# Dx32_V1_0.net
KiCad netlist of a schematic drawn in EAGLE
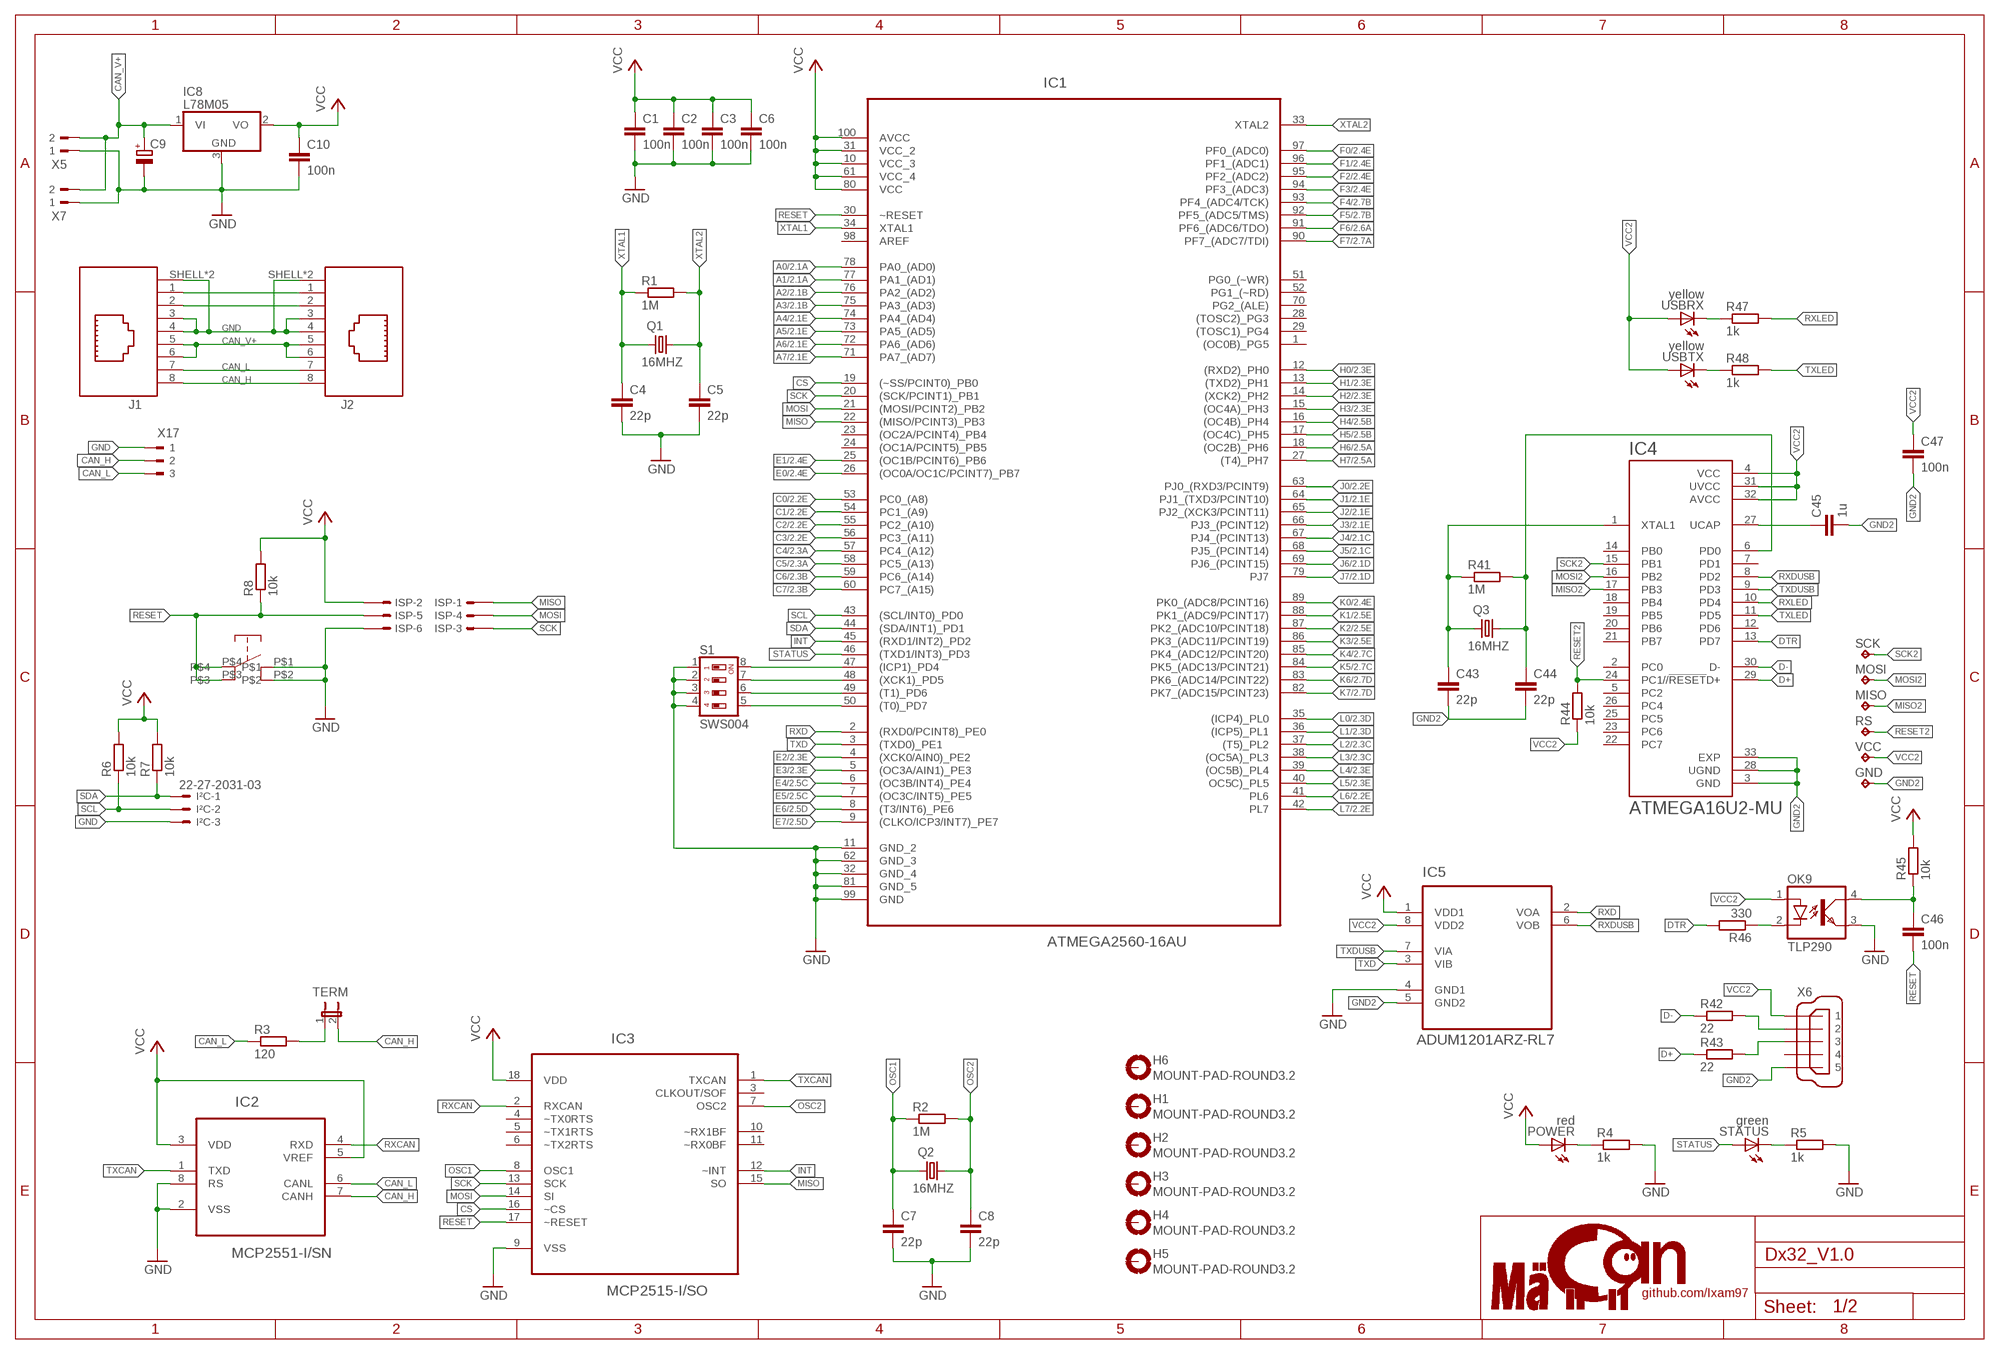
[diagram p0: schematic, sheet 1]
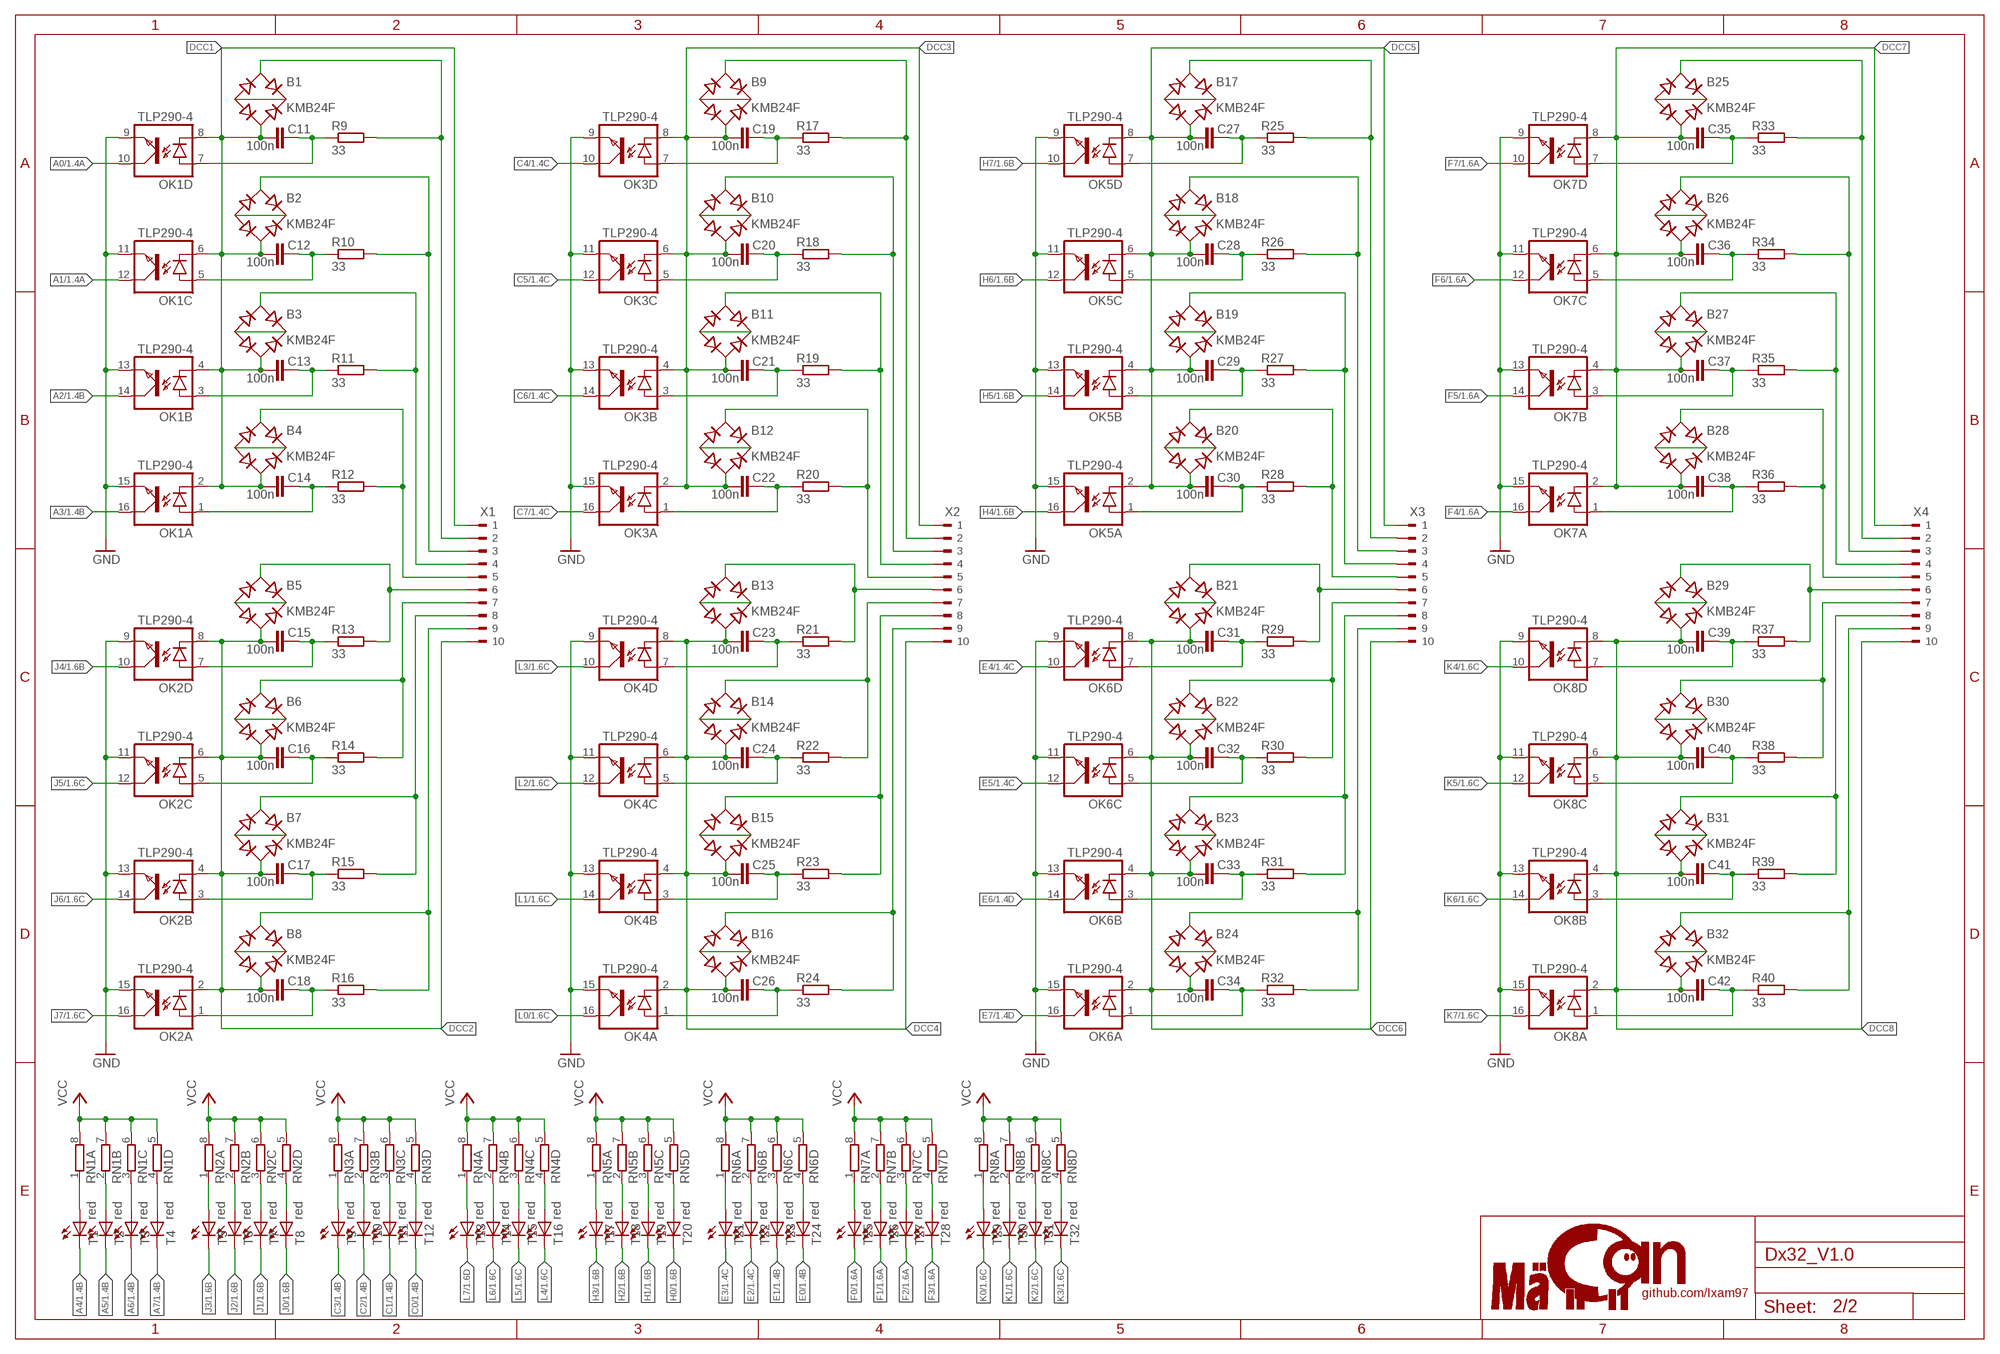
[diagram p1: schematic, sheet 2]

(export (version "E")
  (design (tool "Eeschema 10.0.6"))
  (components
    (comp (ref "C1")
      (value "100n")
      (footprint "eagle-import:C0402")
      (libsource (lib "eagle-import") (part "C-EUC0402"))
    )
    (comp (ref "C2")
      (value "100n")
      (footprint "eagle-import:C0402")
      (libsource (lib "eagle-import") (part "C-EUC0402"))
    )
    (comp (ref "C3")
      (value "100n")
      (footprint "eagle-import:C0402")
      (libsource (lib "eagle-import") (part "C-EUC0402"))
    )
    (comp (ref "C4")
      (value "22p")
      (footprint "eagle-import:C0402")
      (libsource (lib "eagle-import") (part "C-EUC0402"))
    )
    (comp (ref "C5")
      (value "22p")
      (footprint "eagle-import:C0402")
      (libsource (lib "eagle-import") (part "C-EUC0402"))
    )
    (comp (ref "C6")
      (value "100n")
      (footprint "eagle-import:C0402")
      (libsource (lib "eagle-import") (part "C-EUC0402"))
    )
    (comp (ref "C7")
      (value "22p")
      (footprint "eagle-import:C0402")
      (libsource (lib "eagle-import") (part "C-EUC0402"))
    )
    (comp (ref "C8")
      (value "22p")
      (footprint "eagle-import:C0402")
      (libsource (lib "eagle-import") (part "C-EUC0402"))
    )
    (comp (ref "C9")
      (value "CPOL-EUCT3216")
      (footprint "eagle-import:CT3216")
      (libsource (lib "eagle-import") (part "CPOL-EUCT3216"))
    )
    (comp (ref "C10")
      (value "100n")
      (footprint "eagle-import:C0402")
      (libsource (lib "eagle-import") (part "C-EUC0402"))
    )
    (comp (ref "C43")
      (value "22p")
      (footprint "eagle-import:C0402")
      (libsource (lib "eagle-import") (part "C-EUC0402"))
    )
    (comp (ref "C44")
      (value "22p")
      (footprint "eagle-import:C0402")
      (libsource (lib "eagle-import") (part "C-EUC0402"))
    )
    (comp (ref "C45")
      (value "1u")
      (footprint "eagle-import:C0402")
      (libsource (lib "eagle-import") (part "C-EUC0402"))
    )
    (comp (ref "C46")
      (value "100n")
      (footprint "eagle-import:C0402")
      (libsource (lib "eagle-import") (part "C-EUC0402"))
    )
    (comp (ref "C47")
      (value "100n")
      (footprint "eagle-import:C0402")
      (libsource (lib "eagle-import") (part "C-EUC0402"))
    )
    (comp (ref "GND")
      (value "TPB1,27")
      (footprint "eagle-import:B1,27")
      (libsource (lib "eagle-import") (part "TPB1,27"))
    )
    (comp (ref "H1")
      (value "MOUNT-PAD-ROUND3.2")
      (footprint "eagle-import:3,2-PAD")
      (libsource (lib "eagle-import") (part "MOUNT-PAD-ROUND3.2"))
    )
    (comp (ref "H2")
      (value "MOUNT-PAD-ROUND3.2")
      (footprint "eagle-import:3,2-PAD")
      (libsource (lib "eagle-import") (part "MOUNT-PAD-ROUND3.2"))
    )
    (comp (ref "H3")
      (value "MOUNT-PAD-ROUND3.2")
      (footprint "eagle-import:3,2-PAD")
      (libsource (lib "eagle-import") (part "MOUNT-PAD-ROUND3.2"))
    )
    (comp (ref "H4")
      (value "MOUNT-PAD-ROUND3.2")
      (footprint "eagle-import:3,2-PAD")
      (libsource (lib "eagle-import") (part "MOUNT-PAD-ROUND3.2"))
    )
    (comp (ref "H5")
      (value "MOUNT-PAD-ROUND3.2")
      (footprint "eagle-import:3,2-PAD")
      (libsource (lib "eagle-import") (part "MOUNT-PAD-ROUND3.2"))
    )
    (comp (ref "H6")
      (value "MOUNT-PAD-ROUND3.2")
      (footprint "eagle-import:3,2-PAD")
      (libsource (lib "eagle-import") (part "MOUNT-PAD-ROUND3.2"))
    )
    (comp (ref "IC1")
      (value "ATMEGA2560-16AU")
      (footprint "eagle-import:QFP50P1600X1600X120-100N")
      (fields (field (name "MF") "Microchip"))
      (libsource (lib "eagle-import") (part "ATMEGA2560-16AU"))
    )
    (comp (ref "IC2")
      (value "MCP2551-I/SN")
      (footprint "eagle-import:SOIC127P600X175-8N")
      (libsource (lib "eagle-import") (part "MCP2551-I/SN"))
    )
    (comp (ref "IC3")
      (value "MCP2515-I/SO")
      (footprint "eagle-import:SOIC127P1034X264-18N")
      (libsource (lib "eagle-import") (part "MCP2515-I/SO"))
    )
    (comp (ref "IC4")
      (value "ATMEGA16U2-MU")
      (footprint "eagle-import:QFN50P500X500X100-33N")
      (fields (field (name "MF") "Microchip"))
      (libsource (lib "eagle-import") (part "ATMEGA16U2-MU"))
    )
    (comp (ref "IC5")
      (value "ADUM1201ARZ-RL7")
      (footprint "eagle-import:SOIC127P600X175-8N")
      (fields (field (name "MF") "Analog Devices"))
      (libsource (lib "eagle-import") (part "ADUM1201ARZ-RL7"))
    )
    (comp (ref "IC8")
      (value "L78M05")
      (footprint "eagle-import:TO252")
      (fields (field (name "JLCPCB-PART") "C58069"))
      (libsource (lib "eagle-import") (part "78DT05"))
    )
    (comp (ref "ISP")
      (value "057-006-1")
      (footprint "eagle-import:057-006-1")
      (libsource (lib "eagle-import") (part "057-006-1"))
    )
    (comp (ref "I²C")
      (value "22-27-2031-03")
      (footprint "eagle-import:6410-03")
      (fields (field (name "MF") "MOLEX"))
      (libsource (lib "eagle-import") (part "22-?-0327-2031"))
    )
    (comp (ref "J1")
      (value "615008140421")
      (footprint "eagle-import:615008140421")
      (libsource (lib "eagle-import") (part "615008140421"))
    )
    (comp (ref "J2")
      (value "615008140421")
      (footprint "eagle-import:615008140421")
      (libsource (lib "eagle-import") (part "615008140421"))
    )
    (comp (ref "MISO")
      (value "TPB1,27")
      (footprint "eagle-import:B1,27")
      (libsource (lib "eagle-import") (part "TPB1,27"))
    )
    (comp (ref "MOSI")
      (value "TPB1,27")
      (footprint "eagle-import:B1,27")
      (libsource (lib "eagle-import") (part "TPB1,27"))
    )
    (comp (ref "OK9")
      (value "TLP290")
      (footprint "eagle-import:MINI-FLAT-4")
      (libsource (lib "eagle-import") (part "TLP283"))
    )
    (comp (ref "POWER")
      (value "red")
      (footprint "eagle-import:CHIP-LED0805")
      (libsource (lib "eagle-import") (part "LEDCHIP-LED0805"))
    )
    (comp (ref "Q1")
      (value "16MHZ")
      (footprint "eagle-import:3.2X2.5_KX-7")
      (libsource (lib "eagle-import") (part "KX-7"))
    )
    (comp (ref "Q2")
      (value "16MHZ")
      (footprint "eagle-import:3.2X2.5_KX-7")
      (libsource (lib "eagle-import") (part "KX-7"))
    )
    (comp (ref "Q3")
      (value "16MHZ")
      (footprint "eagle-import:3.2X2.5_KX-7")
      (libsource (lib "eagle-import") (part "KX-7"))
    )
    (comp (ref "R1")
      (value "1M")
      (footprint "eagle-import:R0402")
      (libsource (lib "eagle-import") (part "R-EU_R0402"))
    )
    (comp (ref "R2")
      (value "1M")
      (footprint "eagle-import:R0402")
      (libsource (lib "eagle-import") (part "R-EU_R0402"))
    )
    (comp (ref "R3")
      (value "120")
      (footprint "eagle-import:R0402")
      (libsource (lib "eagle-import") (part "R-EU_R0402"))
    )
    (comp (ref "R4")
      (value "1k")
      (footprint "eagle-import:R0402")
      (libsource (lib "eagle-import") (part "R-EU_R0402"))
    )
    (comp (ref "R5")
      (value "1k")
      (footprint "eagle-import:R0402")
      (libsource (lib "eagle-import") (part "R-EU_R0402"))
    )
    (comp (ref "R6")
      (value "10k")
      (footprint "eagle-import:R0402")
      (libsource (lib "eagle-import") (part "R-EU_R0402"))
    )
    (comp (ref "R7")
      (value "10k")
      (footprint "eagle-import:R0402")
      (libsource (lib "eagle-import") (part "R-EU_R0402"))
    )
    (comp (ref "R8")
      (value "10k")
      (footprint "eagle-import:R0402")
      (libsource (lib "eagle-import") (part "R-EU_R0402"))
    )
    (comp (ref "R41")
      (value "1M")
      (footprint "eagle-import:R0402")
      (libsource (lib "eagle-import") (part "R-EU_R0402"))
    )
    (comp (ref "R42")
      (value "22")
      (footprint "eagle-import:R0402")
      (libsource (lib "eagle-import") (part "R-EU_R0402"))
    )
    (comp (ref "R43")
      (value "22")
      (footprint "eagle-import:R0402")
      (libsource (lib "eagle-import") (part "R-EU_R0402"))
    )
    (comp (ref "R44")
      (value "10k")
      (footprint "eagle-import:R0402")
      (libsource (lib "eagle-import") (part "R-EU_R0402"))
    )
    (comp (ref "R45")
      (value "10k")
      (footprint "eagle-import:R0402")
      (libsource (lib "eagle-import") (part "R-EU_R0402"))
    )
    (comp (ref "R46")
      (value "330")
      (footprint "eagle-import:R0402")
      (libsource (lib "eagle-import") (part "R-EU_R0402"))
    )
    (comp (ref "R47")
      (value "1k")
      (footprint "eagle-import:R0402")
      (libsource (lib "eagle-import") (part "R-EU_R0402"))
    )
    (comp (ref "R48")
      (value "1k")
      (footprint "eagle-import:R0402")
      (libsource (lib "eagle-import") (part "R-EU_R0402"))
    )
    (comp (ref "RS")
      (value "TPB1,27")
      (footprint "eagle-import:B1,27")
      (libsource (lib "eagle-import") (part "TPB1,27"))
    )
    (comp (ref "S1")
      (value "SWS004")
      (footprint "eagle-import:SMS-004")
      (libsource (lib "eagle-import") (part "SWS004"))
    )
    (comp (ref "SCK")
      (value "TPB1,27")
      (footprint "eagle-import:B1,27")
      (libsource (lib "eagle-import") (part "TPB1,27"))
    )
    (comp (ref "STATUS")
      (value "green")
      (footprint "eagle-import:CHIP-LED0805")
      (libsource (lib "eagle-import") (part "LEDCHIP-LED0805"))
    )
    (comp (ref "TERM")
      (value "JP1E")
      (footprint "eagle-import:JP1")
      (libsource (lib "eagle-import") (part "JP1E"))
    )
    (comp (ref "U$15")
      (value "BUTTON_JLC")
      (footprint "eagle-import:BUTTON")
      (libsource (lib "eagle-import") (part "BUTTON_JLC"))
    )
    (comp (ref "USBRX")
      (value "yellow")
      (footprint "eagle-import:CHIP-LED0805")
      (libsource (lib "eagle-import") (part "LEDCHIP-LED0805"))
    )
    (comp (ref "USBTX")
      (value "yellow")
      (footprint "eagle-import:CHIP-LED0805")
      (libsource (lib "eagle-import") (part "LEDCHIP-LED0805"))
    )
    (comp (ref "VCC")
      (value "TPB1,27")
      (footprint "eagle-import:B1,27")
      (libsource (lib "eagle-import") (part "TPB1,27"))
    )
    (comp (ref "X5")
      (value "180-2")
      (footprint "eagle-import:180-2")
      (libsource (lib "eagle-import") (part "180-2"))
    )
    (comp (ref "X6")
      (value "MINI-USB_SHIELD5P2-32005-601")
      (footprint "eagle-import:32005-601")
      (libsource (lib "eagle-import") (part "MINI-USB_SHIELD5P2-32005-601"))
    )
    (comp (ref "X7")
      (value "180-2")
      (footprint "eagle-import:180-2")
      (libsource (lib "eagle-import") (part "180-2"))
    )
    (comp (ref "X17")
      (value "180-3")
      (footprint "eagle-import:180-3")
      (libsource (lib "eagle-import") (part "180-3"))
    )
    (comp (ref "B1")
      (value "KMB24F")
      (footprint "eagle-import:MBS")
      (fields (field (name "JLCPCB-PART") "C113927"))
      (libsource (lib "eagle-import") (part "BS2"))
    )
    (comp (ref "B2")
      (value "KMB24F")
      (footprint "eagle-import:MBS")
      (libsource (lib "eagle-import") (part "BS2"))
    )
    (comp (ref "B3")
      (value "KMB24F")
      (footprint "eagle-import:MBS")
      (libsource (lib "eagle-import") (part "BS2"))
    )
    (comp (ref "B4")
      (value "KMB24F")
      (footprint "eagle-import:MBS")
      (libsource (lib "eagle-import") (part "BS2"))
    )
    (comp (ref "B5")
      (value "KMB24F")
      (footprint "eagle-import:MBS")
      (libsource (lib "eagle-import") (part "BS2"))
    )
    (comp (ref "B6")
      (value "KMB24F")
      (footprint "eagle-import:MBS")
      (libsource (lib "eagle-import") (part "BS2"))
    )
    (comp (ref "B7")
      (value "KMB24F")
      (footprint "eagle-import:MBS")
      (libsource (lib "eagle-import") (part "BS2"))
    )
    (comp (ref "B8")
      (value "KMB24F")
      (footprint "eagle-import:MBS")
      (libsource (lib "eagle-import") (part "BS2"))
    )
    (comp (ref "B9")
      (value "KMB24F")
      (footprint "eagle-import:MBS")
      (libsource (lib "eagle-import") (part "BS2"))
    )
    (comp (ref "B10")
      (value "KMB24F")
      (footprint "eagle-import:MBS")
      (libsource (lib "eagle-import") (part "BS2"))
    )
    (comp (ref "B11")
      (value "KMB24F")
      (footprint "eagle-import:MBS")
      (libsource (lib "eagle-import") (part "BS2"))
    )
    (comp (ref "B12")
      (value "KMB24F")
      (footprint "eagle-import:MBS")
      (libsource (lib "eagle-import") (part "BS2"))
    )
    (comp (ref "B13")
      (value "KMB24F")
      (footprint "eagle-import:MBS")
      (libsource (lib "eagle-import") (part "BS2"))
    )
    (comp (ref "B14")
      (value "KMB24F")
      (footprint "eagle-import:MBS")
      (libsource (lib "eagle-import") (part "BS2"))
    )
    (comp (ref "B15")
      (value "KMB24F")
      (footprint "eagle-import:MBS")
      (libsource (lib "eagle-import") (part "BS2"))
    )
    (comp (ref "B16")
      (value "KMB24F")
      (footprint "eagle-import:MBS")
      (libsource (lib "eagle-import") (part "BS2"))
    )
    (comp (ref "B17")
      (value "KMB24F")
      (footprint "eagle-import:MBS")
      (libsource (lib "eagle-import") (part "BS2"))
    )
    (comp (ref "B18")
      (value "KMB24F")
      (footprint "eagle-import:MBS")
      (libsource (lib "eagle-import") (part "BS2"))
    )
    (comp (ref "B19")
      (value "KMB24F")
      (footprint "eagle-import:MBS")
      (libsource (lib "eagle-import") (part "BS2"))
    )
    (comp (ref "B20")
      (value "KMB24F")
      (footprint "eagle-import:MBS")
      (libsource (lib "eagle-import") (part "BS2"))
    )
    (comp (ref "B21")
      (value "KMB24F")
      (footprint "eagle-import:MBS")
      (libsource (lib "eagle-import") (part "BS2"))
    )
    (comp (ref "B22")
      (value "KMB24F")
      (footprint "eagle-import:MBS")
      (libsource (lib "eagle-import") (part "BS2"))
    )
    (comp (ref "B23")
      (value "KMB24F")
      (footprint "eagle-import:MBS")
      (libsource (lib "eagle-import") (part "BS2"))
    )
    (comp (ref "B24")
      (value "KMB24F")
      (footprint "eagle-import:MBS")
      (libsource (lib "eagle-import") (part "BS2"))
    )
    (comp (ref "B25")
      (value "KMB24F")
      (footprint "eagle-import:MBS")
      (libsource (lib "eagle-import") (part "BS2"))
    )
    (comp (ref "B26")
      (value "KMB24F")
      (footprint "eagle-import:MBS")
      (libsource (lib "eagle-import") (part "BS2"))
    )
    (comp (ref "B27")
      (value "KMB24F")
      (footprint "eagle-import:MBS")
      (libsource (lib "eagle-import") (part "BS2"))
    )
    (comp (ref "B28")
      (value "KMB24F")
      (footprint "eagle-import:MBS")
      (libsource (lib "eagle-import") (part "BS2"))
    )
    (comp (ref "B29")
      (value "KMB24F")
      (footprint "eagle-import:MBS")
      (libsource (lib "eagle-import") (part "BS2"))
    )
    (comp (ref "B30")
      (value "KMB24F")
      (footprint "eagle-import:MBS")
      (libsource (lib "eagle-import") (part "BS2"))
    )
    (comp (ref "B31")
      (value "KMB24F")
      (footprint "eagle-import:MBS")
      (libsource (lib "eagle-import") (part "BS2"))
    )
    (comp (ref "B32")
      (value "KMB24F")
      (footprint "eagle-import:MBS")
      (libsource (lib "eagle-import") (part "BS2"))
    )
    (comp (ref "C11")
      (value "100n")
      (footprint "eagle-import:C0402")
      (libsource (lib "eagle-import") (part "C-EUC0402"))
    )
    (comp (ref "C12")
      (value "100n")
      (footprint "eagle-import:C0402")
      (libsource (lib "eagle-import") (part "C-EUC0402"))
    )
    (comp (ref "C13")
      (value "100n")
      (footprint "eagle-import:C0402")
      (libsource (lib "eagle-import") (part "C-EUC0402"))
    )
    (comp (ref "C14")
      (value "100n")
      (footprint "eagle-import:C0402")
      (libsource (lib "eagle-import") (part "C-EUC0402"))
    )
    (comp (ref "C15")
      (value "100n")
      (footprint "eagle-import:C0402")
      (libsource (lib "eagle-import") (part "C-EUC0402"))
    )
    (comp (ref "C16")
      (value "100n")
      (footprint "eagle-import:C0402")
      (libsource (lib "eagle-import") (part "C-EUC0402"))
    )
    (comp (ref "C17")
      (value "100n")
      (footprint "eagle-import:C0402")
      (libsource (lib "eagle-import") (part "C-EUC0402"))
    )
    (comp (ref "C18")
      (value "100n")
      (footprint "eagle-import:C0402")
      (libsource (lib "eagle-import") (part "C-EUC0402"))
    )
    (comp (ref "C19")
      (value "100n")
      (footprint "eagle-import:C0402")
      (libsource (lib "eagle-import") (part "C-EUC0402"))
    )
    (comp (ref "C20")
      (value "100n")
      (footprint "eagle-import:C0402")
      (libsource (lib "eagle-import") (part "C-EUC0402"))
    )
    (comp (ref "C21")
      (value "100n")
      (footprint "eagle-import:C0402")
      (libsource (lib "eagle-import") (part "C-EUC0402"))
    )
    (comp (ref "C22")
      (value "100n")
      (footprint "eagle-import:C0402")
      (libsource (lib "eagle-import") (part "C-EUC0402"))
    )
    (comp (ref "C23")
      (value "100n")
      (footprint "eagle-import:C0402")
      (libsource (lib "eagle-import") (part "C-EUC0402"))
    )
    (comp (ref "C24")
      (value "100n")
      (footprint "eagle-import:C0402")
      (libsource (lib "eagle-import") (part "C-EUC0402"))
    )
    (comp (ref "C25")
      (value "100n")
      (footprint "eagle-import:C0402")
      (libsource (lib "eagle-import") (part "C-EUC0402"))
    )
    (comp (ref "C26")
      (value "100n")
      (footprint "eagle-import:C0402")
      (libsource (lib "eagle-import") (part "C-EUC0402"))
    )
    (comp (ref "C27")
      (value "100n")
      (footprint "eagle-import:C0402")
      (libsource (lib "eagle-import") (part "C-EUC0402"))
    )
    (comp (ref "C28")
      (value "100n")
      (footprint "eagle-import:C0402")
      (libsource (lib "eagle-import") (part "C-EUC0402"))
    )
    (comp (ref "C29")
      (value "100n")
      (footprint "eagle-import:C0402")
      (libsource (lib "eagle-import") (part "C-EUC0402"))
    )
    (comp (ref "C30")
      (value "100n")
      (footprint "eagle-import:C0402")
      (libsource (lib "eagle-import") (part "C-EUC0402"))
    )
    (comp (ref "C31")
      (value "100n")
      (footprint "eagle-import:C0402")
      (libsource (lib "eagle-import") (part "C-EUC0402"))
    )
    (comp (ref "C32")
      (value "100n")
      (footprint "eagle-import:C0402")
      (libsource (lib "eagle-import") (part "C-EUC0402"))
    )
    (comp (ref "C33")
      (value "100n")
      (footprint "eagle-import:C0402")
      (libsource (lib "eagle-import") (part "C-EUC0402"))
    )
    (comp (ref "C34")
      (value "100n")
      (footprint "eagle-import:C0402")
      (libsource (lib "eagle-import") (part "C-EUC0402"))
    )
    (comp (ref "C35")
      (value "100n")
      (footprint "eagle-import:C0402")
      (libsource (lib "eagle-import") (part "C-EUC0402"))
    )
    (comp (ref "C36")
      (value "100n")
      (footprint "eagle-import:C0402")
      (libsource (lib "eagle-import") (part "C-EUC0402"))
    )
    (comp (ref "C37")
      (value "100n")
      (footprint "eagle-import:C0402")
      (libsource (lib "eagle-import") (part "C-EUC0402"))
    )
    (comp (ref "C38")
      (value "100n")
      (footprint "eagle-import:C0402")
      (libsource (lib "eagle-import") (part "C-EUC0402"))
    )
    (comp (ref "C39")
      (value "100n")
      (footprint "eagle-import:C0402")
      (libsource (lib "eagle-import") (part "C-EUC0402"))
    )
    (comp (ref "C40")
      (value "100n")
      (footprint "eagle-import:C0402")
      (libsource (lib "eagle-import") (part "C-EUC0402"))
    )
    (comp (ref "C41")
      (value "100n")
      (footprint "eagle-import:C0402")
      (libsource (lib "eagle-import") (part "C-EUC0402"))
    )
    (comp (ref "C42")
      (value "100n")
      (footprint "eagle-import:C0402")
      (libsource (lib "eagle-import") (part "C-EUC0402"))
    )
    (comp (ref "OK1")
      (value "TLP290-4")
      (footprint "eagle-import:MINI-FLAT-16")
      (fields (field (name "JLCPC-PART") "C39031"))
      (libsource (lib "eagle-import") (part "TLP283-4"))
    )
    (comp (ref "OK2")
      (value "TLP290-4")
      (footprint "eagle-import:MINI-FLAT-16")
      (libsource (lib "eagle-import") (part "TLP283-4"))
    )
    (comp (ref "OK3")
      (value "TLP290-4")
      (footprint "eagle-import:MINI-FLAT-16")
      (libsource (lib "eagle-import") (part "TLP283-4"))
    )
    (comp (ref "OK4")
      (value "TLP290-4")
      (footprint "eagle-import:MINI-FLAT-16")
      (libsource (lib "eagle-import") (part "TLP283-4"))
    )
    (comp (ref "OK5")
      (value "TLP290-4")
      (footprint "eagle-import:MINI-FLAT-16")
      (libsource (lib "eagle-import") (part "TLP283-4"))
    )
    (comp (ref "OK6")
      (value "TLP290-4")
      (footprint "eagle-import:MINI-FLAT-16")
      (libsource (lib "eagle-import") (part "TLP283-4"))
    )
    (comp (ref "OK7")
      (value "TLP290-4")
      (footprint "eagle-import:MINI-FLAT-16")
      (libsource (lib "eagle-import") (part "TLP283-4"))
    )
    (comp (ref "OK8")
      (value "TLP290-4")
      (footprint "eagle-import:MINI-FLAT-16")
      (libsource (lib "eagle-import") (part "TLP283-4"))
    )
    (comp (ref "R9")
      (value "33")
      (footprint "eagle-import:R0402")
      (libsource (lib "eagle-import") (part "R-EU_R0402"))
    )
    (comp (ref "R10")
      (value "33")
      (footprint "eagle-import:R0402")
      (libsource (lib "eagle-import") (part "R-EU_R0402"))
    )
    (comp (ref "R11")
      (value "33")
      (footprint "eagle-import:R0402")
      (libsource (lib "eagle-import") (part "R-EU_R0402"))
    )
    (comp (ref "R12")
      (value "33")
      (footprint "eagle-import:R0402")
      (libsource (lib "eagle-import") (part "R-EU_R0402"))
    )
    (comp (ref "R13")
      (value "33")
      (footprint "eagle-import:R0402")
      (libsource (lib "eagle-import") (part "R-EU_R0402"))
    )
    (comp (ref "R14")
      (value "33")
      (footprint "eagle-import:R0402")
      (libsource (lib "eagle-import") (part "R-EU_R0402"))
    )
    (comp (ref "R15")
      (value "33")
      (footprint "eagle-import:R0402")
      (libsource (lib "eagle-import") (part "R-EU_R0402"))
    )
    (comp (ref "R16")
      (value "33")
      (footprint "eagle-import:R0402")
      (libsource (lib "eagle-import") (part "R-EU_R0402"))
    )
    (comp (ref "R17")
      (value "33")
      (footprint "eagle-import:R0402")
      (libsource (lib "eagle-import") (part "R-EU_R0402"))
    )
    (comp (ref "R18")
      (value "33")
      (footprint "eagle-import:R0402")
      (libsource (lib "eagle-import") (part "R-EU_R0402"))
    )
    (comp (ref "R19")
      (value "33")
      (footprint "eagle-import:R0402")
      (libsource (lib "eagle-import") (part "R-EU_R0402"))
    )
    (comp (ref "R20")
      (value "33")
      (footprint "eagle-import:R0402")
      (libsource (lib "eagle-import") (part "R-EU_R0402"))
    )
    (comp (ref "R21")
      (value "33")
      (footprint "eagle-import:R0402")
      (libsource (lib "eagle-import") (part "R-EU_R0402"))
    )
    (comp (ref "R22")
      (value "33")
      (footprint "eagle-import:R0402")
      (libsource (lib "eagle-import") (part "R-EU_R0402"))
    )
    (comp (ref "R23")
      (value "33")
      (footprint "eagle-import:R0402")
      (libsource (lib "eagle-import") (part "R-EU_R0402"))
    )
    (comp (ref "R24")
      (value "33")
      (footprint "eagle-import:R0402")
      (libsource (lib "eagle-import") (part "R-EU_R0402"))
    )
    (comp (ref "R25")
      (value "33")
      (footprint "eagle-import:R0402")
      (libsource (lib "eagle-import") (part "R-EU_R0402"))
    )
    (comp (ref "R26")
      (value "33")
      (footprint "eagle-import:R0402")
      (libsource (lib "eagle-import") (part "R-EU_R0402"))
    )
    (comp (ref "R27")
      (value "33")
      (footprint "eagle-import:R0402")
      (libsource (lib "eagle-import") (part "R-EU_R0402"))
    )
    (comp (ref "R28")
      (value "33")
      (footprint "eagle-import:R0402")
      (libsource (lib "eagle-import") (part "R-EU_R0402"))
    )
    (comp (ref "R29")
      (value "33")
      (footprint "eagle-import:R0402")
      (libsource (lib "eagle-import") (part "R-EU_R0402"))
    )
    (comp (ref "R30")
      (value "33")
      (footprint "eagle-import:R0402")
      (libsource (lib "eagle-import") (part "R-EU_R0402"))
    )
    (comp (ref "R31")
      (value "33")
      (footprint "eagle-import:R0402")
      (libsource (lib "eagle-import") (part "R-EU_R0402"))
    )
    (comp (ref "R32")
      (value "33")
      (footprint "eagle-import:R0402")
      (libsource (lib "eagle-import") (part "R-EU_R0402"))
    )
    (comp (ref "R33")
      (value "33")
      (footprint "eagle-import:R0402")
      (libsource (lib "eagle-import") (part "R-EU_R0402"))
    )
    (comp (ref "R34")
      (value "33")
      (footprint "eagle-import:R0402")
      (libsource (lib "eagle-import") (part "R-EU_R0402"))
    )
    (comp (ref "R35")
      (value "33")
      (footprint "eagle-import:R0402")
      (libsource (lib "eagle-import") (part "R-EU_R0402"))
    )
    (comp (ref "R36")
      (value "33")
      (footprint "eagle-import:R0402")
      (libsource (lib "eagle-import") (part "R-EU_R0402"))
    )
    (comp (ref "R37")
      (value "33")
      (footprint "eagle-import:R0402")
      (libsource (lib "eagle-import") (part "R-EU_R0402"))
    )
    (comp (ref "R38")
      (value "33")
      (footprint "eagle-import:R0402")
      (libsource (lib "eagle-import") (part "R-EU_R0402"))
    )
    (comp (ref "R39")
      (value "33")
      (footprint "eagle-import:R0402")
      (libsource (lib "eagle-import") (part "R-EU_R0402"))
    )
    (comp (ref "R40")
      (value "33")
      (footprint "eagle-import:R0402")
      (libsource (lib "eagle-import") (part "R-EU_R0402"))
    )
    (comp (ref "RN1")
      (value "4R-N0603-ARV")
      (footprint "eagle-import:0603-ARV")
      (libsource (lib "eagle-import") (part "4R-N0603-ARV"))
    )
    (comp (ref "RN2")
      (value "4R-N0603-ARV")
      (footprint "eagle-import:0603-ARV")
      (libsource (lib "eagle-import") (part "4R-N0603-ARV"))
    )
    (comp (ref "RN3")
      (value "4R-N0603-ARV")
      (footprint "eagle-import:0603-ARV")
      (libsource (lib "eagle-import") (part "4R-N0603-ARV"))
    )
    (comp (ref "RN4")
      (value "4R-N0603-ARV")
      (footprint "eagle-import:0603-ARV")
      (libsource (lib "eagle-import") (part "4R-N0603-ARV"))
    )
    (comp (ref "RN5")
      (value "4R-N0603-ARV")
      (footprint "eagle-import:0603-ARV")
      (libsource (lib "eagle-import") (part "4R-N0603-ARV"))
    )
    (comp (ref "RN6")
      (value "4R-N0603-ARV")
      (footprint "eagle-import:0603-ARV")
      (libsource (lib "eagle-import") (part "4R-N0603-ARV"))
    )
    (comp (ref "RN7")
      (value "4R-N0603-ARV")
      (footprint "eagle-import:0603-ARV")
      (libsource (lib "eagle-import") (part "4R-N0603-ARV"))
    )
    (comp (ref "RN8")
      (value "4R-N0603-ARV")
      (footprint "eagle-import:0603-ARV")
      (libsource (lib "eagle-import") (part "4R-N0603-ARV"))
    )
    (comp (ref "T1")
      (value "red")
      (footprint "eagle-import:CHIP-LED0805")
      (fields (field (name "JLCPCB-PART") "C84256"))
      (libsource (lib "eagle-import") (part "LEDCHIP-LED0805"))
    )
    (comp (ref "T2")
      (value "red")
      (footprint "eagle-import:CHIP-LED0805")
      (libsource (lib "eagle-import") (part "LEDCHIP-LED0805"))
    )
    (comp (ref "T3")
      (value "red")
      (footprint "eagle-import:CHIP-LED0805")
      (libsource (lib "eagle-import") (part "LEDCHIP-LED0805"))
    )
    (comp (ref "T4")
      (value "red")
      (footprint "eagle-import:CHIP-LED0805")
      (libsource (lib "eagle-import") (part "LEDCHIP-LED0805"))
    )
    (comp (ref "T5")
      (value "red")
      (footprint "eagle-import:CHIP-LED0805")
      (libsource (lib "eagle-import") (part "LEDCHIP-LED0805"))
    )
    (comp (ref "T6")
      (value "red")
      (footprint "eagle-import:CHIP-LED0805")
      (libsource (lib "eagle-import") (part "LEDCHIP-LED0805"))
    )
    (comp (ref "T7")
      (value "red")
      (footprint "eagle-import:CHIP-LED0805")
      (libsource (lib "eagle-import") (part "LEDCHIP-LED0805"))
    )
    (comp (ref "T8")
      (value "red")
      (footprint "eagle-import:CHIP-LED0805")
      (libsource (lib "eagle-import") (part "LEDCHIP-LED0805"))
    )
    (comp (ref "T9")
      (value "red")
      (footprint "eagle-import:CHIP-LED0805")
      (libsource (lib "eagle-import") (part "LEDCHIP-LED0805"))
    )
    (comp (ref "T10")
      (value "red")
      (footprint "eagle-import:CHIP-LED0805")
      (libsource (lib "eagle-import") (part "LEDCHIP-LED0805"))
    )
    (comp (ref "T11")
      (value "red")
      (footprint "eagle-import:CHIP-LED0805")
      (libsource (lib "eagle-import") (part "LEDCHIP-LED0805"))
    )
    (comp (ref "T12")
      (value "red")
      (footprint "eagle-import:CHIP-LED0805")
      (libsource (lib "eagle-import") (part "LEDCHIP-LED0805"))
    )
    (comp (ref "T13")
      (value "red")
      (footprint "eagle-import:CHIP-LED0805")
      (libsource (lib "eagle-import") (part "LEDCHIP-LED0805"))
    )
    (comp (ref "T14")
      (value "red")
      (footprint "eagle-import:CHIP-LED0805")
      (libsource (lib "eagle-import") (part "LEDCHIP-LED0805"))
    )
    (comp (ref "T15")
      (value "red")
      (footprint "eagle-import:CHIP-LED0805")
      (libsource (lib "eagle-import") (part "LEDCHIP-LED0805"))
    )
    (comp (ref "T16")
      (value "red")
      (footprint "eagle-import:CHIP-LED0805")
      (libsource (lib "eagle-import") (part "LEDCHIP-LED0805"))
    )
    (comp (ref "T17")
      (value "red")
      (footprint "eagle-import:CHIP-LED0805")
      (libsource (lib "eagle-import") (part "LEDCHIP-LED0805"))
    )
    (comp (ref "T18")
      (value "red")
      (footprint "eagle-import:CHIP-LED0805")
      (libsource (lib "eagle-import") (part "LEDCHIP-LED0805"))
    )
    (comp (ref "T19")
      (value "red")
      (footprint "eagle-import:CHIP-LED0805")
      (libsource (lib "eagle-import") (part "LEDCHIP-LED0805"))
    )
    (comp (ref "T20")
      (value "red")
      (footprint "eagle-import:CHIP-LED0805")
      (libsource (lib "eagle-import") (part "LEDCHIP-LED0805"))
    )
    (comp (ref "T21")
      (value "red")
      (footprint "eagle-import:CHIP-LED0805")
      (libsource (lib "eagle-import") (part "LEDCHIP-LED0805"))
    )
    (comp (ref "T22")
      (value "red")
      (footprint "eagle-import:CHIP-LED0805")
      (libsource (lib "eagle-import") (part "LEDCHIP-LED0805"))
    )
    (comp (ref "T23")
      (value "red")
      (footprint "eagle-import:CHIP-LED0805")
      (libsource (lib "eagle-import") (part "LEDCHIP-LED0805"))
    )
    (comp (ref "T24")
      (value "red")
      (footprint "eagle-import:CHIP-LED0805")
      (libsource (lib "eagle-import") (part "LEDCHIP-LED0805"))
    )
    (comp (ref "T25")
      (value "red")
      (footprint "eagle-import:CHIP-LED0805")
      (libsource (lib "eagle-import") (part "LEDCHIP-LED0805"))
    )
    (comp (ref "T26")
      (value "red")
      (footprint "eagle-import:CHIP-LED0805")
      (libsource (lib "eagle-import") (part "LEDCHIP-LED0805"))
    )
    (comp (ref "T27")
      (value "red")
      (footprint "eagle-import:CHIP-LED0805")
      (libsource (lib "eagle-import") (part "LEDCHIP-LED0805"))
    )
    (comp (ref "T28")
      (value "red")
      (footprint "eagle-import:CHIP-LED0805")
      (libsource (lib "eagle-import") (part "LEDCHIP-LED0805"))
    )
    (comp (ref "T29")
      (value "red")
      (footprint "eagle-import:CHIP-LED0805")
      (libsource (lib "eagle-import") (part "LEDCHIP-LED0805"))
    )
    (comp (ref "T30")
      (value "red")
      (footprint "eagle-import:CHIP-LED0805")
      (libsource (lib "eagle-import") (part "LEDCHIP-LED0805"))
    )
    (comp (ref "T31")
      (value "red")
      (footprint "eagle-import:CHIP-LED0805")
      (libsource (lib "eagle-import") (part "LEDCHIP-LED0805"))
    )
    (comp (ref "T32")
      (value "red")
      (footprint "eagle-import:CHIP-LED0805")
      (libsource (lib "eagle-import") (part "LEDCHIP-LED0805"))
    )
    (comp (ref "X1")
      (value "180-10")
      (footprint "eagle-import:180-10")
      (libsource (lib "eagle-import") (part "180-10"))
    )
    (comp (ref "X2")
      (value "180-10")
      (footprint "eagle-import:180-10")
      (libsource (lib "eagle-import") (part "180-10"))
    )
    (comp (ref "X3")
      (value "180-10")
      (footprint "eagle-import:180-10")
      (libsource (lib "eagle-import") (part "180-10"))
    )
    (comp (ref "X4")
      (value "180-10")
      (footprint "eagle-import:180-10")
      (libsource (lib "eagle-import") (part "180-10"))
    )
  )
  (nets
    (net (code "1") (name "A0") (class "Default")
      (node (ref "IC1") (pin "78") (pinfunction "PA0_(AD0)_78") (pintype "bidirectional"))
      (node (ref "OK1") (pin "10") (pinfunction "COL_10") (pintype "passive"))
    )
    (net (code "2") (name "A1") (class "Default")
      (node (ref "IC1") (pin "77") (pinfunction "PA1_(AD1)_77") (pintype "bidirectional"))
      (node (ref "OK1") (pin "12") (pinfunction "COL_12") (pintype "passive"))
    )
    (net (code "3") (name "A2") (class "Default")
      (node (ref "IC1") (pin "76") (pinfunction "PA2_(AD2)_76") (pintype "bidirectional"))
      (node (ref "OK1") (pin "14") (pinfunction "COL_14") (pintype "passive"))
    )
    (net (code "4") (name "A3") (class "Default")
      (node (ref "IC1") (pin "75") (pinfunction "PA3_(AD3)_75") (pintype "bidirectional"))
      (node (ref "OK1") (pin "16") (pinfunction "COL_16") (pintype "passive"))
    )
    (net (code "5") (name "A4") (class "Default")
      (node (ref "IC1") (pin "74") (pinfunction "PA4_(AD4)_74") (pintype "bidirectional"))
      (node (ref "T1") (pin "C") (pinfunction "C_C") (pintype "passive"))
    )
    (net (code "6") (name "A5") (class "Default")
      (node (ref "IC1") (pin "73") (pinfunction "PA5_(AD5)_73") (pintype "bidirectional"))
      (node (ref "T2") (pin "C") (pinfunction "C_C") (pintype "passive"))
    )
    (net (code "7") (name "A6") (class "Default")
      (node (ref "IC1") (pin "72") (pinfunction "PA6_(AD6)_72") (pintype "bidirectional"))
      (node (ref "T3") (pin "C") (pinfunction "C_C") (pintype "passive"))
    )
    (net (code "8") (name "A7") (class "Default")
      (node (ref "IC1") (pin "71") (pinfunction "PA7_(AD7)_71") (pintype "bidirectional"))
      (node (ref "T4") (pin "C") (pinfunction "C_C") (pintype "passive"))
    )
    (net (code "9") (name "C0") (class "Default")
      (node (ref "IC1") (pin "53") (pinfunction "PC0_(A8)_53") (pintype "bidirectional"))
      (node (ref "T12") (pin "C") (pinfunction "C_C") (pintype "passive"))
    )
    (net (code "10") (name "C1") (class "Default")
      (node (ref "IC1") (pin "54") (pinfunction "PC1_(A9)_54") (pintype "bidirectional"))
      (node (ref "T11") (pin "C") (pinfunction "C_C") (pintype "passive"))
    )
    (net (code "11") (name "C2") (class "Default")
      (node (ref "IC1") (pin "55") (pinfunction "PC2_(A10)_55") (pintype "bidirectional"))
      (node (ref "T10") (pin "C") (pinfunction "C_C") (pintype "passive"))
    )
    (net (code "12") (name "C3") (class "Default")
      (node (ref "IC1") (pin "56") (pinfunction "PC3_(A11)_56") (pintype "bidirectional"))
      (node (ref "T9") (pin "C") (pinfunction "C_C") (pintype "passive"))
    )
    (net (code "13") (name "C4") (class "Default")
      (node (ref "IC1") (pin "57") (pinfunction "PC4_(A12)_57") (pintype "bidirectional"))
      (node (ref "OK3") (pin "10") (pinfunction "COL_10") (pintype "passive"))
    )
    (net (code "14") (name "C5") (class "Default")
      (node (ref "IC1") (pin "58") (pinfunction "PC5_(A13)_58") (pintype "bidirectional"))
      (node (ref "OK3") (pin "12") (pinfunction "COL_12") (pintype "passive"))
    )
    (net (code "15") (name "C6") (class "Default")
      (node (ref "IC1") (pin "59") (pinfunction "PC6_(A14)_59") (pintype "bidirectional"))
      (node (ref "OK3") (pin "14") (pinfunction "COL_14") (pintype "passive"))
    )
    (net (code "16") (name "C7") (class "Default")
      (node (ref "IC1") (pin "60") (pinfunction "PC7_(A15)_60") (pintype "bidirectional"))
      (node (ref "OK3") (pin "16") (pinfunction "COL_16") (pintype "passive"))
    )
    (net (code "17") (name "CAN_H") (class "Default")
      (node (ref "IC2") (pin "7") (pinfunction "CANH_7") (pintype "bidirectional"))
      (node (ref "J1") (pin "8") (pinfunction "8_8") (pintype "passive"))
      (node (ref "J2") (pin "8") (pinfunction "8_8") (pintype "passive"))
      (node (ref "TERM") (pin "2") (pinfunction "2_2") (pintype "passive"))
      (node (ref "X17") (pin "2") (pinfunction "2_2") (pintype "passive"))
    )
    (net (code "18") (name "CAN_L") (class "Default")
      (node (ref "IC2") (pin "6") (pinfunction "CANL_6") (pintype "bidirectional"))
      (node (ref "J1") (pin "7") (pinfunction "7_7") (pintype "passive"))
      (node (ref "J2") (pin "7") (pinfunction "7_7") (pintype "passive"))
      (node (ref "R3") (pin "1") (pinfunction "1_1") (pintype "passive"))
      (node (ref "X17") (pin "3") (pinfunction "3_3") (pintype "passive"))
    )
    (net (code "19") (name "CAN_V+") (class "Default")
      (node (ref "C9") (pin "+") (pinfunction "+_+") (pintype "passive"))
      (node (ref "IC8") (pin "1") (pinfunction "VI_1") (pintype "input"))
      (node (ref "J1") (pin "5") (pinfunction "5_5") (pintype "passive"))
      (node (ref "J1") (pin "6") (pinfunction "6_6") (pintype "passive"))
      (node (ref "J2") (pin "5") (pinfunction "5_5") (pintype "passive"))
      (node (ref "J2") (pin "6") (pinfunction "6_6") (pintype "passive"))
      (node (ref "X5") (pin "2") (pinfunction "2_2") (pintype "passive"))
      (node (ref "X7") (pin "2") (pinfunction "2_2") (pintype "passive"))
    )
    (net (code "20") (name "CS") (class "Default")
      (node (ref "IC1") (pin "19") (pinfunction "(~{SS/PCINT0})_PB0_19") (pintype "bidirectional"))
      (node (ref "IC3") (pin "16") (pinfunction "~{CS}_16") (pintype "input"))
    )
    (net (code "21") (name "D+") (class "Default")
      (node (ref "IC4") (pin "29") (pinfunction "D+_29") (pintype "bidirectional"))
      (node (ref "R43") (pin "1") (pinfunction "1_1") (pintype "passive"))
    )
    (net (code "22") (name "D-") (class "Default")
      (node (ref "IC4") (pin "30") (pinfunction "D-_30") (pintype "bidirectional"))
      (node (ref "R42") (pin "1") (pinfunction "1_1") (pintype "passive"))
    )
    (net (code "23") (name "DCC1") (class "Default")
      (node (ref "B1") (pin "AC2") (pinfunction "AC2_AC2") (pintype "passive"))
      (node (ref "B2") (pin "AC2") (pinfunction "AC2_AC2") (pintype "passive"))
      (node (ref "B3") (pin "AC2") (pinfunction "AC2_AC2") (pintype "passive"))
      (node (ref "B4") (pin "AC2") (pinfunction "AC2_AC2") (pintype "passive"))
      (node (ref "C11") (pin "2") (pinfunction "2_2") (pintype "passive"))
      (node (ref "C12") (pin "2") (pinfunction "2_2") (pintype "passive"))
      (node (ref "C13") (pin "2") (pinfunction "2_2") (pintype "passive"))
      (node (ref "C14") (pin "2") (pinfunction "2_2") (pintype "passive"))
      (node (ref "OK1") (pin "2") (pinfunction "C_2") (pintype "passive"))
      (node (ref "OK1") (pin "4") (pinfunction "C_4") (pintype "passive"))
      (node (ref "OK1") (pin "6") (pinfunction "C_6") (pintype "passive"))
      (node (ref "OK1") (pin "8") (pinfunction "C_8") (pintype "passive"))
      (node (ref "X1") (pin "1") (pinfunction "1_1") (pintype "passive"))
    )
    (net (code "24") (name "DCC2") (class "Default")
      (node (ref "B5") (pin "AC2") (pinfunction "AC2_AC2") (pintype "passive"))
      (node (ref "B6") (pin "AC2") (pinfunction "AC2_AC2") (pintype "passive"))
      (node (ref "B7") (pin "AC2") (pinfunction "AC2_AC2") (pintype "passive"))
      (node (ref "B8") (pin "AC2") (pinfunction "AC2_AC2") (pintype "passive"))
      (node (ref "C15") (pin "2") (pinfunction "2_2") (pintype "passive"))
      (node (ref "C16") (pin "2") (pinfunction "2_2") (pintype "passive"))
      (node (ref "C17") (pin "2") (pinfunction "2_2") (pintype "passive"))
      (node (ref "C18") (pin "2") (pinfunction "2_2") (pintype "passive"))
      (node (ref "OK2") (pin "2") (pinfunction "C_2") (pintype "passive"))
      (node (ref "OK2") (pin "4") (pinfunction "C_4") (pintype "passive"))
      (node (ref "OK2") (pin "6") (pinfunction "C_6") (pintype "passive"))
      (node (ref "OK2") (pin "8") (pinfunction "C_8") (pintype "passive"))
      (node (ref "X1") (pin "10") (pinfunction "10_10") (pintype "passive"))
    )
    (net (code "25") (name "DCC3") (class "Default")
      (node (ref "B10") (pin "AC2") (pinfunction "AC2_AC2") (pintype "passive"))
      (node (ref "B11") (pin "AC2") (pinfunction "AC2_AC2") (pintype "passive"))
      (node (ref "B12") (pin "AC2") (pinfunction "AC2_AC2") (pintype "passive"))
      (node (ref "B9") (pin "AC2") (pinfunction "AC2_AC2") (pintype "passive"))
      (node (ref "C19") (pin "2") (pinfunction "2_2") (pintype "passive"))
      (node (ref "C20") (pin "2") (pinfunction "2_2") (pintype "passive"))
      (node (ref "C21") (pin "2") (pinfunction "2_2") (pintype "passive"))
      (node (ref "C22") (pin "2") (pinfunction "2_2") (pintype "passive"))
      (node (ref "OK3") (pin "2") (pinfunction "C_2") (pintype "passive"))
      (node (ref "OK3") (pin "4") (pinfunction "C_4") (pintype "passive"))
      (node (ref "OK3") (pin "6") (pinfunction "C_6") (pintype "passive"))
      (node (ref "OK3") (pin "8") (pinfunction "C_8") (pintype "passive"))
      (node (ref "X2") (pin "1") (pinfunction "1_1") (pintype "passive"))
    )
    (net (code "26") (name "DCC4") (class "Default")
      (node (ref "B13") (pin "AC2") (pinfunction "AC2_AC2") (pintype "passive"))
      (node (ref "B14") (pin "AC2") (pinfunction "AC2_AC2") (pintype "passive"))
      (node (ref "B15") (pin "AC2") (pinfunction "AC2_AC2") (pintype "passive"))
      (node (ref "B16") (pin "AC2") (pinfunction "AC2_AC2") (pintype "passive"))
      (node (ref "C23") (pin "2") (pinfunction "2_2") (pintype "passive"))
      (node (ref "C24") (pin "2") (pinfunction "2_2") (pintype "passive"))
      (node (ref "C25") (pin "2") (pinfunction "2_2") (pintype "passive"))
      (node (ref "C26") (pin "2") (pinfunction "2_2") (pintype "passive"))
      (node (ref "OK4") (pin "2") (pinfunction "C_2") (pintype "passive"))
      (node (ref "OK4") (pin "4") (pinfunction "C_4") (pintype "passive"))
      (node (ref "OK4") (pin "6") (pinfunction "C_6") (pintype "passive"))
      (node (ref "OK4") (pin "8") (pinfunction "C_8") (pintype "passive"))
      (node (ref "X2") (pin "10") (pinfunction "10_10") (pintype "passive"))
    )
    (net (code "27") (name "DCC5") (class "Default")
      (node (ref "B17") (pin "AC2") (pinfunction "AC2_AC2") (pintype "passive"))
      (node (ref "B18") (pin "AC2") (pinfunction "AC2_AC2") (pintype "passive"))
      (node (ref "B19") (pin "AC2") (pinfunction "AC2_AC2") (pintype "passive"))
      (node (ref "B20") (pin "AC2") (pinfunction "AC2_AC2") (pintype "passive"))
      (node (ref "C27") (pin "2") (pinfunction "2_2") (pintype "passive"))
      (node (ref "C28") (pin "2") (pinfunction "2_2") (pintype "passive"))
      (node (ref "C29") (pin "2") (pinfunction "2_2") (pintype "passive"))
      (node (ref "C30") (pin "2") (pinfunction "2_2") (pintype "passive"))
      (node (ref "OK5") (pin "2") (pinfunction "C_2") (pintype "passive"))
      (node (ref "OK5") (pin "4") (pinfunction "C_4") (pintype "passive"))
      (node (ref "OK5") (pin "6") (pinfunction "C_6") (pintype "passive"))
      (node (ref "OK5") (pin "8") (pinfunction "C_8") (pintype "passive"))
      (node (ref "X3") (pin "1") (pinfunction "1_1") (pintype "passive"))
    )
    (net (code "28") (name "DCC6") (class "Default")
      (node (ref "B21") (pin "AC2") (pinfunction "AC2_AC2") (pintype "passive"))
      (node (ref "B22") (pin "AC2") (pinfunction "AC2_AC2") (pintype "passive"))
      (node (ref "B23") (pin "AC2") (pinfunction "AC2_AC2") (pintype "passive"))
      (node (ref "B24") (pin "AC2") (pinfunction "AC2_AC2") (pintype "passive"))
      (node (ref "C31") (pin "2") (pinfunction "2_2") (pintype "passive"))
      (node (ref "C32") (pin "2") (pinfunction "2_2") (pintype "passive"))
      (node (ref "C33") (pin "2") (pinfunction "2_2") (pintype "passive"))
      (node (ref "C34") (pin "2") (pinfunction "2_2") (pintype "passive"))
      (node (ref "OK6") (pin "2") (pinfunction "C_2") (pintype "passive"))
      (node (ref "OK6") (pin "4") (pinfunction "C_4") (pintype "passive"))
      (node (ref "OK6") (pin "6") (pinfunction "C_6") (pintype "passive"))
      (node (ref "OK6") (pin "8") (pinfunction "C_8") (pintype "passive"))
      (node (ref "X3") (pin "10") (pinfunction "10_10") (pintype "passive"))
    )
    (net (code "29") (name "DCC7") (class "Default")
      (node (ref "B25") (pin "AC2") (pinfunction "AC2_AC2") (pintype "passive"))
      (node (ref "B26") (pin "AC2") (pinfunction "AC2_AC2") (pintype "passive"))
      (node (ref "B27") (pin "AC2") (pinfunction "AC2_AC2") (pintype "passive"))
      (node (ref "B28") (pin "AC2") (pinfunction "AC2_AC2") (pintype "passive"))
      (node (ref "C35") (pin "2") (pinfunction "2_2") (pintype "passive"))
      (node (ref "C36") (pin "2") (pinfunction "2_2") (pintype "passive"))
      (node (ref "C37") (pin "2") (pinfunction "2_2") (pintype "passive"))
      (node (ref "C38") (pin "2") (pinfunction "2_2") (pintype "passive"))
      (node (ref "OK7") (pin "2") (pinfunction "C_2") (pintype "passive"))
      (node (ref "OK7") (pin "4") (pinfunction "C_4") (pintype "passive"))
      (node (ref "OK7") (pin "6") (pinfunction "C_6") (pintype "passive"))
      (node (ref "OK7") (pin "8") (pinfunction "C_8") (pintype "passive"))
      (node (ref "X4") (pin "1") (pinfunction "1_1") (pintype "passive"))
    )
    (net (code "30") (name "DCC8") (class "Default")
      (node (ref "B29") (pin "AC2") (pinfunction "AC2_AC2") (pintype "passive"))
      (node (ref "B30") (pin "AC2") (pinfunction "AC2_AC2") (pintype "passive"))
      (node (ref "B31") (pin "AC2") (pinfunction "AC2_AC2") (pintype "passive"))
      (node (ref "B32") (pin "AC2") (pinfunction "AC2_AC2") (pintype "passive"))
      (node (ref "C39") (pin "2") (pinfunction "2_2") (pintype "passive"))
      (node (ref "C40") (pin "2") (pinfunction "2_2") (pintype "passive"))
      (node (ref "C41") (pin "2") (pinfunction "2_2") (pintype "passive"))
      (node (ref "C42") (pin "2") (pinfunction "2_2") (pintype "passive"))
      (node (ref "OK8") (pin "2") (pinfunction "C_2") (pintype "passive"))
      (node (ref "OK8") (pin "4") (pinfunction "C_4") (pintype "passive"))
      (node (ref "OK8") (pin "6") (pinfunction "C_6") (pintype "passive"))
      (node (ref "OK8") (pin "8") (pinfunction "C_8") (pintype "passive"))
      (node (ref "X4") (pin "10") (pinfunction "10_10") (pintype "passive"))
    )
    (net (code "31") (name "DTR") (class "Default")
      (node (ref "IC4") (pin "13") (pinfunction "PD7_13") (pintype "bidirectional"))
      (node (ref "R46") (pin "2") (pinfunction "2_2") (pintype "passive"))
    )
    (net (code "32") (name "E0") (class "Default")
      (node (ref "IC1") (pin "26") (pinfunction "(OC0A/OC1C/PCINT7)_PB7_26") (pintype "bidirectional"))
      (node (ref "T24") (pin "C") (pinfunction "C_C") (pintype "passive"))
    )
    (net (code "33") (name "E1") (class "Default")
      (node (ref "IC1") (pin "25") (pinfunction "(OC1B/PCINT6)_PB6_25") (pintype "bidirectional"))
      (node (ref "T23") (pin "C") (pinfunction "C_C") (pintype "passive"))
    )
    (net (code "34") (name "E2") (class "Default")
      (node (ref "IC1") (pin "4") (pinfunction "(XCK0/AIN0)_PE2_4") (pintype "bidirectional"))
      (node (ref "T22") (pin "C") (pinfunction "C_C") (pintype "passive"))
    )
    (net (code "35") (name "E3") (class "Default")
      (node (ref "IC1") (pin "5") (pinfunction "(OC3A/AIN1)_PE3_5") (pintype "bidirectional"))
      (node (ref "T21") (pin "C") (pinfunction "C_C") (pintype "passive"))
    )
    (net (code "36") (name "E4") (class "Default")
      (node (ref "IC1") (pin "6") (pinfunction "(OC3B/INT4)_PE4_6") (pintype "bidirectional"))
      (node (ref "OK6") (pin "10") (pinfunction "COL_10") (pintype "passive"))
    )
    (net (code "37") (name "E5") (class "Default")
      (node (ref "IC1") (pin "7") (pinfunction "(OC3C/INT5)_PE5_7") (pintype "bidirectional"))
      (node (ref "OK6") (pin "12") (pinfunction "COL_12") (pintype "passive"))
    )
    (net (code "38") (name "E6") (class "Default")
      (node (ref "IC1") (pin "8") (pinfunction "(T3/INT6)_PE6_8") (pintype "bidirectional"))
      (node (ref "OK6") (pin "14") (pinfunction "COL_14") (pintype "passive"))
    )
    (net (code "39") (name "E7") (class "Default")
      (node (ref "IC1") (pin "9") (pinfunction "(CLKO/ICP3/INT7)_PE7_9") (pintype "bidirectional"))
      (node (ref "OK6") (pin "16") (pinfunction "COL_16") (pintype "passive"))
    )
    (net (code "40") (name "F0") (class "Default")
      (node (ref "IC1") (pin "97") (pinfunction "PF0_(ADC0)_97") (pintype "bidirectional"))
      (node (ref "T25") (pin "C") (pinfunction "C_C") (pintype "passive"))
    )
    (net (code "41") (name "F1") (class "Default")
      (node (ref "IC1") (pin "96") (pinfunction "PF1_(ADC1)_96") (pintype "bidirectional"))
      (node (ref "T26") (pin "C") (pinfunction "C_C") (pintype "passive"))
    )
    (net (code "42") (name "F2") (class "Default")
      (node (ref "IC1") (pin "95") (pinfunction "PF2_(ADC2)_95") (pintype "bidirectional"))
      (node (ref "T27") (pin "C") (pinfunction "C_C") (pintype "passive"))
    )
    (net (code "43") (name "F3") (class "Default")
      (node (ref "IC1") (pin "94") (pinfunction "PF3_(ADC3)_94") (pintype "bidirectional"))
      (node (ref "T28") (pin "C") (pinfunction "C_C") (pintype "passive"))
    )
    (net (code "44") (name "F4") (class "Default")
      (node (ref "IC1") (pin "93") (pinfunction "PF4_(ADC4/TCK)_93") (pintype "bidirectional"))
      (node (ref "OK7") (pin "16") (pinfunction "COL_16") (pintype "passive"))
    )
    (net (code "45") (name "F5") (class "Default")
      (node (ref "IC1") (pin "92") (pinfunction "PF5_(ADC5/TMS)_92") (pintype "bidirectional"))
      (node (ref "OK7") (pin "14") (pinfunction "COL_14") (pintype "passive"))
    )
    (net (code "46") (name "F6") (class "Default")
      (node (ref "IC1") (pin "91") (pinfunction "PF6_(ADC6/TDO)_91") (pintype "bidirectional"))
      (node (ref "OK7") (pin "12") (pinfunction "COL_12") (pintype "passive"))
    )
    (net (code "47") (name "F7") (class "Default")
      (node (ref "IC1") (pin "90") (pinfunction "PF7_(ADC7/TDI)_90") (pintype "bidirectional"))
      (node (ref "OK7") (pin "10") (pinfunction "COL_10") (pintype "passive"))
    )
    (net (code "48") (name "GND") (class "Default")
      (node (ref "C1") (pin "2") (pinfunction "2_2") (pintype "passive"))
      (node (ref "C10") (pin "2") (pinfunction "2_2") (pintype "passive"))
      (node (ref "C2") (pin "2") (pinfunction "2_2") (pintype "passive"))
      (node (ref "C3") (pin "2") (pinfunction "2_2") (pintype "passive"))
      (node (ref "C4") (pin "2") (pinfunction "2_2") (pintype "passive"))
      (node (ref "C5") (pin "2") (pinfunction "2_2") (pintype "passive"))
      (node (ref "C6") (pin "2") (pinfunction "2_2") (pintype "passive"))
      (node (ref "C7") (pin "2") (pinfunction "2_2") (pintype "passive"))
      (node (ref "C8") (pin "2") (pinfunction "2_2") (pintype "passive"))
      (node (ref "C9") (pin "-") (pinfunction "-_-") (pintype "passive"))
      (node (ref "IC1") (pin "11") (pinfunction "GND_2_11") (pintype "passive"))
      (node (ref "IC1") (pin "32") (pinfunction "GND_4_32") (pintype "passive"))
      (node (ref "IC1") (pin "62") (pinfunction "GND_3_62") (pintype "passive"))
      (node (ref "IC1") (pin "81") (pinfunction "GND_5_81") (pintype "passive"))
      (node (ref "IC1") (pin "99") (pinfunction "GND_99") (pintype "passive"))
      (node (ref "IC2") (pin "2") (pinfunction "VSS_2") (pintype "passive"))
      (node (ref "IC2") (pin "8") (pinfunction "RS_8") (pintype "input"))
      (node (ref "IC3") (pin "9") (pinfunction "VSS_9") (pintype "power_in"))
      (node (ref "IC5") (pin "4") (pinfunction "GND1_4") (pintype "passive"))
      (node (ref "IC8") (pin "3") (pinfunction "GND_3") (pintype "passive"))
      (node (ref "ISP") (pin "6") (pinfunction "S_6") (pintype "passive"))
      (node (ref "I²C") (pin "3") (pinfunction "S_3") (pintype "passive"))
      (node (ref "J1") (pin "3") (pinfunction "3_3") (pintype "passive"))
      (node (ref "J1") (pin "4") (pinfunction "4_4") (pintype "passive"))
      (node (ref "J1") (pin "SHELL") (pinfunction "SHIELD_SHELL") (pintype "passive"))
      (node (ref "J1") (pin "SHELL1") (pinfunction "SHIELD_SHELL1") (pintype "passive"))
      (node (ref "J2") (pin "3") (pinfunction "3_3") (pintype "passive"))
      (node (ref "J2") (pin "4") (pinfunction "4_4") (pintype "passive"))
      (node (ref "J2") (pin "SHELL") (pinfunction "SHIELD_SHELL") (pintype "passive"))
      (node (ref "J2") (pin "SHELL1") (pinfunction "SHIELD_SHELL1") (pintype "passive"))
      (node (ref "OK1") (pin "11") (pinfunction "EMIT_11") (pintype "passive"))
      (node (ref "OK1") (pin "13") (pinfunction "EMIT_13") (pintype "passive"))
      (node (ref "OK1") (pin "15") (pinfunction "EMIT_15") (pintype "passive"))
      (node (ref "OK1") (pin "9") (pinfunction "EMIT_9") (pintype "passive"))
      (node (ref "OK2") (pin "11") (pinfunction "EMIT_11") (pintype "passive"))
      (node (ref "OK2") (pin "13") (pinfunction "EMIT_13") (pintype "passive"))
      (node (ref "OK2") (pin "15") (pinfunction "EMIT_15") (pintype "passive"))
      (node (ref "OK2") (pin "9") (pinfunction "EMIT_9") (pintype "passive"))
      (node (ref "OK3") (pin "11") (pinfunction "EMIT_11") (pintype "passive"))
      (node (ref "OK3") (pin "13") (pinfunction "EMIT_13") (pintype "passive"))
      (node (ref "OK3") (pin "15") (pinfunction "EMIT_15") (pintype "passive"))
      (node (ref "OK3") (pin "9") (pinfunction "EMIT_9") (pintype "passive"))
      (node (ref "OK4") (pin "11") (pinfunction "EMIT_11") (pintype "passive"))
      (node (ref "OK4") (pin "13") (pinfunction "EMIT_13") (pintype "passive"))
      (node (ref "OK4") (pin "15") (pinfunction "EMIT_15") (pintype "passive"))
      (node (ref "OK4") (pin "9") (pinfunction "EMIT_9") (pintype "passive"))
      (node (ref "OK5") (pin "11") (pinfunction "EMIT_11") (pintype "passive"))
      (node (ref "OK5") (pin "13") (pinfunction "EMIT_13") (pintype "passive"))
      (node (ref "OK5") (pin "15") (pinfunction "EMIT_15") (pintype "passive"))
      (node (ref "OK5") (pin "9") (pinfunction "EMIT_9") (pintype "passive"))
      (node (ref "OK6") (pin "11") (pinfunction "EMIT_11") (pintype "passive"))
      (node (ref "OK6") (pin "13") (pinfunction "EMIT_13") (pintype "passive"))
      (node (ref "OK6") (pin "15") (pinfunction "EMIT_15") (pintype "passive"))
      (node (ref "OK6") (pin "9") (pinfunction "EMIT_9") (pintype "passive"))
      (node (ref "OK7") (pin "11") (pinfunction "EMIT_11") (pintype "passive"))
      (node (ref "OK7") (pin "13") (pinfunction "EMIT_13") (pintype "passive"))
      (node (ref "OK7") (pin "15") (pinfunction "EMIT_15") (pintype "passive"))
      (node (ref "OK7") (pin "9") (pinfunction "EMIT_9") (pintype "passive"))
      (node (ref "OK8") (pin "11") (pinfunction "EMIT_11") (pintype "passive"))
      (node (ref "OK8") (pin "13") (pinfunction "EMIT_13") (pintype "passive"))
      (node (ref "OK8") (pin "15") (pinfunction "EMIT_15") (pintype "passive"))
      (node (ref "OK8") (pin "9") (pinfunction "EMIT_9") (pintype "passive"))
      (node (ref "OK9") (pin "3") (pinfunction "EMIT_3") (pintype "passive"))
      (node (ref "R4") (pin "2") (pinfunction "2_2") (pintype "passive"))
      (node (ref "R5") (pin "2") (pinfunction "2_2") (pintype "passive"))
      (node (ref "S1") (pin "1") (pinfunction "1_1") (pintype "passive"))
      (node (ref "S1") (pin "2") (pinfunction "2_2") (pintype "passive"))
      (node (ref "S1") (pin "3") (pinfunction "3_3") (pintype "passive"))
      (node (ref "S1") (pin "4") (pinfunction "4_4") (pintype "passive"))
      (node (ref "U$15") (pin "P$1") (pinfunction "P$1_P$1") (pintype "bidirectional"))
      (node (ref "U$15") (pin "P$2") (pinfunction "P$2_P$2") (pintype "bidirectional"))
      (node (ref "X17") (pin "1") (pinfunction "1_1") (pintype "passive"))
      (node (ref "X5") (pin "1") (pinfunction "1_1") (pintype "passive"))
      (node (ref "X7") (pin "1") (pinfunction "1_1") (pintype "passive"))
    )
    (net (code "49") (name "GND2") (class "Default")
      (node (ref "C43") (pin "2") (pinfunction "2_2") (pintype "passive"))
      (node (ref "C44") (pin "2") (pinfunction "2_2") (pintype "passive"))
      (node (ref "C45") (pin "2") (pinfunction "2_2") (pintype "passive"))
      (node (ref "C47") (pin "2") (pinfunction "2_2") (pintype "passive"))
      (node (ref "GND") (pin "TP") (pinfunction "TP_TP") (pintype "input"))
      (node (ref "IC4") (pin "28") (pinfunction "UGND_28") (pintype "power_in"))
      (node (ref "IC4") (pin "3") (pinfunction "GND_3") (pintype "power_in"))
      (node (ref "IC4") (pin "33") (pinfunction "EXP_33") (pintype "power_in"))
      (node (ref "IC5") (pin "5") (pinfunction "GND2_5") (pintype "passive"))
      (node (ref "X6") (pin "5") (pinfunction "5_5") (pintype "passive"))
    )
    (net (code "50") (name "H0") (class "Default")
      (node (ref "IC1") (pin "12") (pinfunction "(RXD2)_PH0_12") (pintype "bidirectional"))
      (node (ref "T20") (pin "C") (pinfunction "C_C") (pintype "passive"))
    )
    (net (code "51") (name "H1") (class "Default")
      (node (ref "IC1") (pin "13") (pinfunction "(TXD2)_PH1_13") (pintype "bidirectional"))
      (node (ref "T19") (pin "C") (pinfunction "C_C") (pintype "passive"))
    )
    (net (code "52") (name "H2") (class "Default")
      (node (ref "IC1") (pin "14") (pinfunction "(XCK2)_PH2_14") (pintype "bidirectional"))
      (node (ref "T18") (pin "C") (pinfunction "C_C") (pintype "passive"))
    )
    (net (code "53") (name "H3") (class "Default")
      (node (ref "IC1") (pin "15") (pinfunction "(OC4A)_PH3_15") (pintype "bidirectional"))
      (node (ref "T17") (pin "C") (pinfunction "C_C") (pintype "passive"))
    )
    (net (code "54") (name "H4") (class "Default")
      (node (ref "IC1") (pin "16") (pinfunction "(OC4B)_PH4_16") (pintype "bidirectional"))
      (node (ref "OK5") (pin "16") (pinfunction "COL_16") (pintype "passive"))
    )
    (net (code "55") (name "H5") (class "Default")
      (node (ref "IC1") (pin "17") (pinfunction "(OC4C)_PH5_17") (pintype "bidirectional"))
      (node (ref "OK5") (pin "14") (pinfunction "COL_14") (pintype "passive"))
    )
    (net (code "56") (name "H6") (class "Default")
      (node (ref "IC1") (pin "18") (pinfunction "(OC2B)_PH6_18") (pintype "bidirectional"))
      (node (ref "OK5") (pin "12") (pinfunction "COL_12") (pintype "passive"))
    )
    (net (code "57") (name "H7") (class "Default")
      (node (ref "IC1") (pin "27") (pinfunction "(T4)_PH7_27") (pintype "bidirectional"))
      (node (ref "OK5") (pin "10") (pinfunction "COL_10") (pintype "passive"))
    )
    (net (code "58") (name "INT") (class "Default")
      (node (ref "IC1") (pin "45") (pinfunction "(RXD1/INT2)_PD2_45") (pintype "bidirectional"))
      (node (ref "IC3") (pin "12") (pinfunction "~{INT}_12") (pintype "output"))
    )
    (net (code "59") (name "J0") (class "Default")
      (node (ref "IC1") (pin "63") (pinfunction "PJ0_(RXD3/PCINT9)_63") (pintype "bidirectional"))
      (node (ref "T8") (pin "C") (pinfunction "C_C") (pintype "passive"))
    )
    (net (code "60") (name "J1") (class "Default")
      (node (ref "IC1") (pin "64") (pinfunction "PJ1_(TXD3/PCINT10)_64") (pintype "bidirectional"))
      (node (ref "T7") (pin "C") (pinfunction "C_C") (pintype "passive"))
    )
    (net (code "61") (name "J2") (class "Default")
      (node (ref "IC1") (pin "65") (pinfunction "PJ2_(XCK3/PCINT11)_65") (pintype "bidirectional"))
      (node (ref "T6") (pin "C") (pinfunction "C_C") (pintype "passive"))
    )
    (net (code "62") (name "J3") (class "Default")
      (node (ref "IC1") (pin "66") (pinfunction "PJ3_(PCINT12)_66") (pintype "bidirectional"))
      (node (ref "T5") (pin "C") (pinfunction "C_C") (pintype "passive"))
    )
    (net (code "63") (name "J4") (class "Default")
      (node (ref "IC1") (pin "67") (pinfunction "PJ4_(PCINT13)_67") (pintype "bidirectional"))
      (node (ref "OK2") (pin "10") (pinfunction "COL_10") (pintype "passive"))
    )
    (net (code "64") (name "J5") (class "Default")
      (node (ref "IC1") (pin "68") (pinfunction "PJ5_(PCINT14)_68") (pintype "bidirectional"))
      (node (ref "OK2") (pin "12") (pinfunction "COL_12") (pintype "passive"))
    )
    (net (code "65") (name "J6") (class "Default")
      (node (ref "IC1") (pin "69") (pinfunction "PJ6_(PCINT15)_69") (pintype "bidirectional"))
      (node (ref "OK2") (pin "14") (pinfunction "COL_14") (pintype "passive"))
    )
    (net (code "66") (name "J7") (class "Default")
      (node (ref "IC1") (pin "79") (pinfunction "PJ7_79") (pintype "bidirectional"))
      (node (ref "OK2") (pin "16") (pinfunction "COL_16") (pintype "passive"))
    )
    (net (code "67") (name "K0") (class "Default")
      (node (ref "IC1") (pin "89") (pinfunction "PK0_(ADC8/PCINT16)_89") (pintype "bidirectional"))
      (node (ref "T29") (pin "C") (pinfunction "C_C") (pintype "passive"))
    )
    (net (code "68") (name "K1") (class "Default")
      (node (ref "IC1") (pin "88") (pinfunction "PK1_(ADC9/PCINT17)_88") (pintype "bidirectional"))
      (node (ref "T30") (pin "C") (pinfunction "C_C") (pintype "passive"))
    )
    (net (code "69") (name "K2") (class "Default")
      (node (ref "IC1") (pin "87") (pinfunction "PK2_(ADC10/PCINT18)_87") (pintype "bidirectional"))
      (node (ref "T31") (pin "C") (pinfunction "C_C") (pintype "passive"))
    )
    (net (code "70") (name "K3") (class "Default")
      (node (ref "IC1") (pin "86") (pinfunction "PK3_(ADC11/PCINT19)_86") (pintype "bidirectional"))
      (node (ref "T32") (pin "C") (pinfunction "C_C") (pintype "passive"))
    )
    (net (code "71") (name "K4") (class "Default")
      (node (ref "IC1") (pin "85") (pinfunction "PK4_(ADC12/PCINT20)_85") (pintype "bidirectional"))
      (node (ref "OK8") (pin "10") (pinfunction "COL_10") (pintype "passive"))
    )
    (net (code "72") (name "K5") (class "Default")
      (node (ref "IC1") (pin "84") (pinfunction "PK5_(ADC13/PCINT21)_84") (pintype "bidirectional"))
      (node (ref "OK8") (pin "12") (pinfunction "COL_12") (pintype "passive"))
    )
    (net (code "73") (name "K6") (class "Default")
      (node (ref "IC1") (pin "83") (pinfunction "PK6_(ADC14/PCINT22)_83") (pintype "bidirectional"))
      (node (ref "OK8") (pin "14") (pinfunction "COL_14") (pintype "passive"))
    )
    (net (code "74") (name "K7") (class "Default")
      (node (ref "IC1") (pin "82") (pinfunction "PK7_(ADC15/PCINT23)_82") (pintype "bidirectional"))
      (node (ref "OK8") (pin "16") (pinfunction "COL_16") (pintype "passive"))
    )
    (net (code "75") (name "L0") (class "Default")
      (node (ref "IC1") (pin "35") (pinfunction "(ICP4)_PL0_35") (pintype "bidirectional"))
      (node (ref "OK4") (pin "16") (pinfunction "COL_16") (pintype "passive"))
    )
    (net (code "76") (name "L1") (class "Default")
      (node (ref "IC1") (pin "36") (pinfunction "(ICP5)_PL1_36") (pintype "bidirectional"))
      (node (ref "OK4") (pin "14") (pinfunction "COL_14") (pintype "passive"))
    )
    (net (code "77") (name "L2") (class "Default")
      (node (ref "IC1") (pin "37") (pinfunction "(T5)_PL2_37") (pintype "bidirectional"))
      (node (ref "OK4") (pin "12") (pinfunction "COL_12") (pintype "passive"))
    )
    (net (code "78") (name "L3") (class "Default")
      (node (ref "IC1") (pin "38") (pinfunction "(OC5A)_PL3_38") (pintype "bidirectional"))
      (node (ref "OK4") (pin "10") (pinfunction "COL_10") (pintype "passive"))
    )
    (net (code "79") (name "L4") (class "Default")
      (node (ref "IC1") (pin "39") (pinfunction "(OC5B)_PL4_39") (pintype "bidirectional"))
      (node (ref "T16") (pin "C") (pinfunction "C_C") (pintype "passive"))
    )
    (net (code "80") (name "L5") (class "Default")
      (node (ref "IC1") (pin "40") (pinfunction "OC5C)_PL5_40") (pintype "bidirectional"))
      (node (ref "T15") (pin "C") (pinfunction "C_C") (pintype "passive"))
    )
    (net (code "81") (name "L6") (class "Default")
      (node (ref "IC1") (pin "41") (pinfunction "PL6_41") (pintype "bidirectional"))
      (node (ref "T14") (pin "C") (pinfunction "C_C") (pintype "passive"))
    )
    (net (code "82") (name "L7") (class "Default")
      (node (ref "IC1") (pin "42") (pinfunction "PL7_42") (pintype "bidirectional"))
      (node (ref "T13") (pin "C") (pinfunction "C_C") (pintype "passive"))
    )
    (net (code "83") (name "MISO") (class "Default")
      (node (ref "IC1") (pin "22") (pinfunction "(MISO/PCINT3)_PB3_22") (pintype "bidirectional"))
      (node (ref "IC3") (pin "15") (pinfunction "SO_15") (pintype "output"))
      (node (ref "ISP") (pin "1") (pinfunction "S_1") (pintype "passive"))
    )
    (net (code "84") (name "MISO2") (class "Default")
      (node (ref "IC4") (pin "17") (pinfunction "PB3_17") (pintype "bidirectional"))
      (node (ref "MISO") (pin "TP") (pinfunction "TP_TP") (pintype "input"))
    )
    (net (code "85") (name "MOSI") (class "Default")
      (node (ref "IC1") (pin "21") (pinfunction "(MOSI/PCINT2)_PB2_21") (pintype "bidirectional"))
      (node (ref "IC3") (pin "14") (pinfunction "SI_14") (pintype "input"))
      (node (ref "ISP") (pin "4") (pinfunction "S_4") (pintype "passive"))
    )
    (net (code "86") (name "MOSI2") (class "Default")
      (node (ref "IC4") (pin "16") (pinfunction "PB2_16") (pintype "bidirectional"))
      (node (ref "MOSI") (pin "TP") (pinfunction "TP_TP") (pintype "input"))
    )
    (net (code "87") (name "Net-(B1-Pad+)") (class "Default")
      (node (ref "B1") (pin "+") (pinfunction "+_+") (pintype "passive"))
      (node (ref "B1") (pin "-") (pinfunction "-_-") (pintype "passive"))
    )
    (net (code "88") (name "Net-(B1-PadAC1)") (class "Default")
      (node (ref "B1") (pin "AC1") (pinfunction "AC1_AC1") (pintype "passive"))
      (node (ref "R9") (pin "2") (pinfunction "2_2") (pintype "passive"))
      (node (ref "X1") (pin "2") (pinfunction "2_2") (pintype "passive"))
    )
    (net (code "89") (name "Net-(B2-Pad+)") (class "Default")
      (node (ref "B2") (pin "+") (pinfunction "+_+") (pintype "passive"))
      (node (ref "B2") (pin "-") (pinfunction "-_-") (pintype "passive"))
    )
    (net (code "90") (name "Net-(B2-PadAC1)") (class "Default")
      (node (ref "B2") (pin "AC1") (pinfunction "AC1_AC1") (pintype "passive"))
      (node (ref "R10") (pin "2") (pinfunction "2_2") (pintype "passive"))
      (node (ref "X1") (pin "3") (pinfunction "3_3") (pintype "passive"))
    )
    (net (code "91") (name "Net-(B3-Pad+)") (class "Default")
      (node (ref "B3") (pin "+") (pinfunction "+_+") (pintype "passive"))
      (node (ref "B3") (pin "-") (pinfunction "-_-") (pintype "passive"))
    )
    (net (code "92") (name "Net-(B3-PadAC1)") (class "Default")
      (node (ref "B3") (pin "AC1") (pinfunction "AC1_AC1") (pintype "passive"))
      (node (ref "R11") (pin "2") (pinfunction "2_2") (pintype "passive"))
      (node (ref "X1") (pin "4") (pinfunction "4_4") (pintype "passive"))
    )
    (net (code "93") (name "Net-(B4-Pad+)") (class "Default")
      (node (ref "B4") (pin "+") (pinfunction "+_+") (pintype "passive"))
      (node (ref "B4") (pin "-") (pinfunction "-_-") (pintype "passive"))
    )
    (net (code "94") (name "Net-(B4-PadAC1)") (class "Default")
      (node (ref "B4") (pin "AC1") (pinfunction "AC1_AC1") (pintype "passive"))
      (node (ref "R12") (pin "2") (pinfunction "2_2") (pintype "passive"))
      (node (ref "X1") (pin "5") (pinfunction "5_5") (pintype "passive"))
    )
    (net (code "95") (name "Net-(B5-Pad+)") (class "Default")
      (node (ref "B5") (pin "+") (pinfunction "+_+") (pintype "passive"))
      (node (ref "B5") (pin "-") (pinfunction "-_-") (pintype "passive"))
    )
    (net (code "96") (name "Net-(B5-PadAC1)") (class "Default")
      (node (ref "B5") (pin "AC1") (pinfunction "AC1_AC1") (pintype "passive"))
      (node (ref "R13") (pin "2") (pinfunction "2_2") (pintype "passive"))
      (node (ref "X1") (pin "6") (pinfunction "6_6") (pintype "passive"))
    )
    (net (code "97") (name "Net-(B6-Pad+)") (class "Default")
      (node (ref "B6") (pin "+") (pinfunction "+_+") (pintype "passive"))
      (node (ref "B6") (pin "-") (pinfunction "-_-") (pintype "passive"))
    )
    (net (code "98") (name "Net-(B6-PadAC1)") (class "Default")
      (node (ref "B6") (pin "AC1") (pinfunction "AC1_AC1") (pintype "passive"))
      (node (ref "R14") (pin "2") (pinfunction "2_2") (pintype "passive"))
      (node (ref "X1") (pin "7") (pinfunction "7_7") (pintype "passive"))
    )
    (net (code "99") (name "Net-(B7-Pad+)") (class "Default")
      (node (ref "B7") (pin "+") (pinfunction "+_+") (pintype "passive"))
      (node (ref "B7") (pin "-") (pinfunction "-_-") (pintype "passive"))
    )
    (net (code "100") (name "Net-(B7-PadAC1)") (class "Default")
      (node (ref "B7") (pin "AC1") (pinfunction "AC1_AC1") (pintype "passive"))
      (node (ref "R15") (pin "2") (pinfunction "2_2") (pintype "passive"))
      (node (ref "X1") (pin "8") (pinfunction "8_8") (pintype "passive"))
    )
    (net (code "101") (name "Net-(B8-Pad+)") (class "Default")
      (node (ref "B8") (pin "+") (pinfunction "+_+") (pintype "passive"))
      (node (ref "B8") (pin "-") (pinfunction "-_-") (pintype "passive"))
    )
    (net (code "102") (name "Net-(B8-PadAC1)") (class "Default")
      (node (ref "B8") (pin "AC1") (pinfunction "AC1_AC1") (pintype "passive"))
      (node (ref "R16") (pin "2") (pinfunction "2_2") (pintype "passive"))
      (node (ref "X1") (pin "9") (pinfunction "9_9") (pintype "passive"))
    )
    (net (code "103") (name "Net-(B9-Pad+)") (class "Default")
      (node (ref "B9") (pin "+") (pinfunction "+_+") (pintype "passive"))
      (node (ref "B9") (pin "-") (pinfunction "-_-") (pintype "passive"))
    )
    (net (code "104") (name "Net-(B9-PadAC1)") (class "Default")
      (node (ref "B9") (pin "AC1") (pinfunction "AC1_AC1") (pintype "passive"))
      (node (ref "R17") (pin "2") (pinfunction "2_2") (pintype "passive"))
      (node (ref "X2") (pin "2") (pinfunction "2_2") (pintype "passive"))
    )
    (net (code "105") (name "Net-(B10-Pad+)") (class "Default")
      (node (ref "B10") (pin "+") (pinfunction "+_+") (pintype "passive"))
      (node (ref "B10") (pin "-") (pinfunction "-_-") (pintype "passive"))
    )
    (net (code "106") (name "Net-(B10-PadAC1)") (class "Default")
      (node (ref "B10") (pin "AC1") (pinfunction "AC1_AC1") (pintype "passive"))
      (node (ref "R18") (pin "2") (pinfunction "2_2") (pintype "passive"))
      (node (ref "X2") (pin "3") (pinfunction "3_3") (pintype "passive"))
    )
    (net (code "107") (name "Net-(B11-Pad+)") (class "Default")
      (node (ref "B11") (pin "+") (pinfunction "+_+") (pintype "passive"))
      (node (ref "B11") (pin "-") (pinfunction "-_-") (pintype "passive"))
    )
    (net (code "108") (name "Net-(B11-PadAC1)") (class "Default")
      (node (ref "B11") (pin "AC1") (pinfunction "AC1_AC1") (pintype "passive"))
      (node (ref "R19") (pin "2") (pinfunction "2_2") (pintype "passive"))
      (node (ref "X2") (pin "4") (pinfunction "4_4") (pintype "passive"))
    )
    (net (code "109") (name "Net-(B12-Pad+)") (class "Default")
      (node (ref "B12") (pin "+") (pinfunction "+_+") (pintype "passive"))
      (node (ref "B12") (pin "-") (pinfunction "-_-") (pintype "passive"))
    )
    (net (code "110") (name "Net-(B12-PadAC1)") (class "Default")
      (node (ref "B12") (pin "AC1") (pinfunction "AC1_AC1") (pintype "passive"))
      (node (ref "R20") (pin "2") (pinfunction "2_2") (pintype "passive"))
      (node (ref "X2") (pin "5") (pinfunction "5_5") (pintype "passive"))
    )
    (net (code "111") (name "Net-(B13-Pad+)") (class "Default")
      (node (ref "B13") (pin "+") (pinfunction "+_+") (pintype "passive"))
      (node (ref "B13") (pin "-") (pinfunction "-_-") (pintype "passive"))
    )
    (net (code "112") (name "Net-(B13-PadAC1)") (class "Default")
      (node (ref "B13") (pin "AC1") (pinfunction "AC1_AC1") (pintype "passive"))
      (node (ref "R21") (pin "2") (pinfunction "2_2") (pintype "passive"))
      (node (ref "X2") (pin "6") (pinfunction "6_6") (pintype "passive"))
    )
    (net (code "113") (name "Net-(B14-Pad+)") (class "Default")
      (node (ref "B14") (pin "+") (pinfunction "+_+") (pintype "passive"))
      (node (ref "B14") (pin "-") (pinfunction "-_-") (pintype "passive"))
    )
    (net (code "114") (name "Net-(B14-PadAC1)") (class "Default")
      (node (ref "B14") (pin "AC1") (pinfunction "AC1_AC1") (pintype "passive"))
      (node (ref "R22") (pin "2") (pinfunction "2_2") (pintype "passive"))
      (node (ref "X2") (pin "7") (pinfunction "7_7") (pintype "passive"))
    )
    (net (code "115") (name "Net-(B15-Pad+)") (class "Default")
      (node (ref "B15") (pin "+") (pinfunction "+_+") (pintype "passive"))
      (node (ref "B15") (pin "-") (pinfunction "-_-") (pintype "passive"))
    )
    (net (code "116") (name "Net-(B15-PadAC1)") (class "Default")
      (node (ref "B15") (pin "AC1") (pinfunction "AC1_AC1") (pintype "passive"))
      (node (ref "R23") (pin "2") (pinfunction "2_2") (pintype "passive"))
      (node (ref "X2") (pin "8") (pinfunction "8_8") (pintype "passive"))
    )
    (net (code "117") (name "Net-(B16-Pad+)") (class "Default")
      (node (ref "B16") (pin "+") (pinfunction "+_+") (pintype "passive"))
      (node (ref "B16") (pin "-") (pinfunction "-_-") (pintype "passive"))
    )
    (net (code "118") (name "Net-(B16-PadAC1)") (class "Default")
      (node (ref "B16") (pin "AC1") (pinfunction "AC1_AC1") (pintype "passive"))
      (node (ref "R24") (pin "2") (pinfunction "2_2") (pintype "passive"))
      (node (ref "X2") (pin "9") (pinfunction "9_9") (pintype "passive"))
    )
    (net (code "119") (name "Net-(B17-Pad+)") (class "Default")
      (node (ref "B17") (pin "+") (pinfunction "+_+") (pintype "passive"))
      (node (ref "B17") (pin "-") (pinfunction "-_-") (pintype "passive"))
    )
    (net (code "120") (name "Net-(B17-PadAC1)") (class "Default")
      (node (ref "B17") (pin "AC1") (pinfunction "AC1_AC1") (pintype "passive"))
      (node (ref "R25") (pin "2") (pinfunction "2_2") (pintype "passive"))
      (node (ref "X3") (pin "2") (pinfunction "2_2") (pintype "passive"))
    )
    (net (code "121") (name "Net-(B18-Pad+)") (class "Default")
      (node (ref "B18") (pin "+") (pinfunction "+_+") (pintype "passive"))
      (node (ref "B18") (pin "-") (pinfunction "-_-") (pintype "passive"))
    )
    (net (code "122") (name "Net-(B18-PadAC1)") (class "Default")
      (node (ref "B18") (pin "AC1") (pinfunction "AC1_AC1") (pintype "passive"))
      (node (ref "R26") (pin "2") (pinfunction "2_2") (pintype "passive"))
      (node (ref "X3") (pin "3") (pinfunction "3_3") (pintype "passive"))
    )
    (net (code "123") (name "Net-(B19-Pad+)") (class "Default")
      (node (ref "B19") (pin "+") (pinfunction "+_+") (pintype "passive"))
      (node (ref "B19") (pin "-") (pinfunction "-_-") (pintype "passive"))
    )
    (net (code "124") (name "Net-(B19-PadAC1)") (class "Default")
      (node (ref "B19") (pin "AC1") (pinfunction "AC1_AC1") (pintype "passive"))
      (node (ref "R27") (pin "2") (pinfunction "2_2") (pintype "passive"))
      (node (ref "X3") (pin "4") (pinfunction "4_4") (pintype "passive"))
    )
    (net (code "125") (name "Net-(B20-Pad+)") (class "Default")
      (node (ref "B20") (pin "+") (pinfunction "+_+") (pintype "passive"))
      (node (ref "B20") (pin "-") (pinfunction "-_-") (pintype "passive"))
    )
    (net (code "126") (name "Net-(B20-PadAC1)") (class "Default")
      (node (ref "B20") (pin "AC1") (pinfunction "AC1_AC1") (pintype "passive"))
      (node (ref "R28") (pin "2") (pinfunction "2_2") (pintype "passive"))
      (node (ref "X3") (pin "5") (pinfunction "5_5") (pintype "passive"))
    )
    (net (code "127") (name "Net-(B21-Pad+)") (class "Default")
      (node (ref "B21") (pin "+") (pinfunction "+_+") (pintype "passive"))
      (node (ref "B21") (pin "-") (pinfunction "-_-") (pintype "passive"))
    )
    (net (code "128") (name "Net-(B21-PadAC1)") (class "Default")
      (node (ref "B21") (pin "AC1") (pinfunction "AC1_AC1") (pintype "passive"))
      (node (ref "R29") (pin "2") (pinfunction "2_2") (pintype "passive"))
      (node (ref "X3") (pin "6") (pinfunction "6_6") (pintype "passive"))
    )
    (net (code "129") (name "Net-(B22-Pad+)") (class "Default")
      (node (ref "B22") (pin "+") (pinfunction "+_+") (pintype "passive"))
      (node (ref "B22") (pin "-") (pinfunction "-_-") (pintype "passive"))
    )
    (net (code "130") (name "Net-(B22-PadAC1)") (class "Default")
      (node (ref "B22") (pin "AC1") (pinfunction "AC1_AC1") (pintype "passive"))
      (node (ref "R30") (pin "2") (pinfunction "2_2") (pintype "passive"))
      (node (ref "X3") (pin "7") (pinfunction "7_7") (pintype "passive"))
    )
    (net (code "131") (name "Net-(B23-Pad+)") (class "Default")
      (node (ref "B23") (pin "+") (pinfunction "+_+") (pintype "passive"))
      (node (ref "B23") (pin "-") (pinfunction "-_-") (pintype "passive"))
    )
    (net (code "132") (name "Net-(B23-PadAC1)") (class "Default")
      (node (ref "B23") (pin "AC1") (pinfunction "AC1_AC1") (pintype "passive"))
      (node (ref "R31") (pin "2") (pinfunction "2_2") (pintype "passive"))
      (node (ref "X3") (pin "8") (pinfunction "8_8") (pintype "passive"))
    )
    (net (code "133") (name "Net-(B24-Pad+)") (class "Default")
      (node (ref "B24") (pin "+") (pinfunction "+_+") (pintype "passive"))
      (node (ref "B24") (pin "-") (pinfunction "-_-") (pintype "passive"))
    )
    (net (code "134") (name "Net-(B24-PadAC1)") (class "Default")
      (node (ref "B24") (pin "AC1") (pinfunction "AC1_AC1") (pintype "passive"))
      (node (ref "R32") (pin "2") (pinfunction "2_2") (pintype "passive"))
      (node (ref "X3") (pin "9") (pinfunction "9_9") (pintype "passive"))
    )
    (net (code "135") (name "Net-(B25-Pad+)") (class "Default")
      (node (ref "B25") (pin "+") (pinfunction "+_+") (pintype "passive"))
      (node (ref "B25") (pin "-") (pinfunction "-_-") (pintype "passive"))
    )
    (net (code "136") (name "Net-(B25-PadAC1)") (class "Default")
      (node (ref "B25") (pin "AC1") (pinfunction "AC1_AC1") (pintype "passive"))
      (node (ref "R33") (pin "2") (pinfunction "2_2") (pintype "passive"))
      (node (ref "X4") (pin "2") (pinfunction "2_2") (pintype "passive"))
    )
    (net (code "137") (name "Net-(B26-Pad+)") (class "Default")
      (node (ref "B26") (pin "+") (pinfunction "+_+") (pintype "passive"))
      (node (ref "B26") (pin "-") (pinfunction "-_-") (pintype "passive"))
    )
    (net (code "138") (name "Net-(B26-PadAC1)") (class "Default")
      (node (ref "B26") (pin "AC1") (pinfunction "AC1_AC1") (pintype "passive"))
      (node (ref "R34") (pin "2") (pinfunction "2_2") (pintype "passive"))
      (node (ref "X4") (pin "3") (pinfunction "3_3") (pintype "passive"))
    )
    (net (code "139") (name "Net-(B27-Pad+)") (class "Default")
      (node (ref "B27") (pin "+") (pinfunction "+_+") (pintype "passive"))
      (node (ref "B27") (pin "-") (pinfunction "-_-") (pintype "passive"))
    )
    (net (code "140") (name "Net-(B27-PadAC1)") (class "Default")
      (node (ref "B27") (pin "AC1") (pinfunction "AC1_AC1") (pintype "passive"))
      (node (ref "R35") (pin "2") (pinfunction "2_2") (pintype "passive"))
      (node (ref "X4") (pin "4") (pinfunction "4_4") (pintype "passive"))
    )
    (net (code "141") (name "Net-(B28-Pad+)") (class "Default")
      (node (ref "B28") (pin "+") (pinfunction "+_+") (pintype "passive"))
      (node (ref "B28") (pin "-") (pinfunction "-_-") (pintype "passive"))
    )
    (net (code "142") (name "Net-(B28-PadAC1)") (class "Default")
      (node (ref "B28") (pin "AC1") (pinfunction "AC1_AC1") (pintype "passive"))
      (node (ref "R36") (pin "2") (pinfunction "2_2") (pintype "passive"))
      (node (ref "X4") (pin "5") (pinfunction "5_5") (pintype "passive"))
    )
    (net (code "143") (name "Net-(B29-Pad+)") (class "Default")
      (node (ref "B29") (pin "+") (pinfunction "+_+") (pintype "passive"))
      (node (ref "B29") (pin "-") (pinfunction "-_-") (pintype "passive"))
    )
    (net (code "144") (name "Net-(B29-PadAC1)") (class "Default")
      (node (ref "B29") (pin "AC1") (pinfunction "AC1_AC1") (pintype "passive"))
      (node (ref "R37") (pin "2") (pinfunction "2_2") (pintype "passive"))
      (node (ref "X4") (pin "6") (pinfunction "6_6") (pintype "passive"))
    )
    (net (code "145") (name "Net-(B30-Pad+)") (class "Default")
      (node (ref "B30") (pin "+") (pinfunction "+_+") (pintype "passive"))
      (node (ref "B30") (pin "-") (pinfunction "-_-") (pintype "passive"))
    )
    (net (code "146") (name "Net-(B30-PadAC1)") (class "Default")
      (node (ref "B30") (pin "AC1") (pinfunction "AC1_AC1") (pintype "passive"))
      (node (ref "R38") (pin "2") (pinfunction "2_2") (pintype "passive"))
      (node (ref "X4") (pin "7") (pinfunction "7_7") (pintype "passive"))
    )
    (net (code "147") (name "Net-(B31-Pad+)") (class "Default")
      (node (ref "B31") (pin "+") (pinfunction "+_+") (pintype "passive"))
      (node (ref "B31") (pin "-") (pinfunction "-_-") (pintype "passive"))
    )
    (net (code "148") (name "Net-(B31-PadAC1)") (class "Default")
      (node (ref "B31") (pin "AC1") (pinfunction "AC1_AC1") (pintype "passive"))
      (node (ref "R39") (pin "2") (pinfunction "2_2") (pintype "passive"))
      (node (ref "X4") (pin "8") (pinfunction "8_8") (pintype "passive"))
    )
    (net (code "149") (name "Net-(B32-Pad+)") (class "Default")
      (node (ref "B32") (pin "+") (pinfunction "+_+") (pintype "passive"))
      (node (ref "B32") (pin "-") (pinfunction "-_-") (pintype "passive"))
    )
    (net (code "150") (name "Net-(B32-PadAC1)") (class "Default")
      (node (ref "B32") (pin "AC1") (pinfunction "AC1_AC1") (pintype "passive"))
      (node (ref "R40") (pin "2") (pinfunction "2_2") (pintype "passive"))
      (node (ref "X4") (pin "9") (pinfunction "9_9") (pintype "passive"))
    )
    (net (code "151") (name "Net-(IC1-(ICP1)_PD4)") (class "Default")
      (node (ref "IC1") (pin "47") (pinfunction "(ICP1)_PD4_47") (pintype "bidirectional"))
      (node (ref "S1") (pin "8") (pinfunction "8_8") (pintype "passive"))
    )
    (net (code "152") (name "Net-(IC1-(T0)_PD7)") (class "Default")
      (node (ref "IC1") (pin "50") (pinfunction "(T0)_PD7_50") (pintype "bidirectional"))
      (node (ref "S1") (pin "5") (pinfunction "5_5") (pintype "passive"))
    )
    (net (code "153") (name "Net-(IC1-(T1)_PD6)") (class "Default")
      (node (ref "IC1") (pin "49") (pinfunction "(T1)_PD6_49") (pintype "bidirectional"))
      (node (ref "S1") (pin "6") (pinfunction "6_6") (pintype "passive"))
    )
    (net (code "154") (name "Net-(IC1-(XCK1)_PD5)") (class "Default")
      (node (ref "IC1") (pin "48") (pinfunction "(XCK1)_PD5_48") (pintype "bidirectional"))
      (node (ref "S1") (pin "7") (pinfunction "7_7") (pintype "passive"))
    )
    (net (code "155") (name "Net-(IC4-PD0)") (class "Default")
      (node (ref "C44") (pin "1") (pinfunction "1_1") (pintype "passive"))
      (node (ref "IC4") (pin "6") (pinfunction "PD0_6") (pintype "bidirectional"))
      (node (ref "Q3") (pin "3") (pinfunction "2_3") (pintype "passive"))
      (node (ref "R41") (pin "2") (pinfunction "2_2") (pintype "passive"))
    )
    (net (code "156") (name "Net-(IC4-UCAP)") (class "Default")
      (node (ref "C45") (pin "1") (pinfunction "1_1") (pintype "passive"))
      (node (ref "IC4") (pin "27") (pinfunction "UCAP_27") (pintype "output"))
    )
    (net (code "157") (name "Net-(IC4-XTAL1)") (class "Default")
      (node (ref "C43") (pin "1") (pinfunction "1_1") (pintype "passive"))
      (node (ref "IC4") (pin "1") (pinfunction "XTAL1_1") (pintype "input"))
      (node (ref "Q3") (pin "1") (pinfunction "1_1") (pintype "passive"))
      (node (ref "R41") (pin "1") (pinfunction "1_1") (pintype "passive"))
    )
    (net (code "158") (name "Net-(J1-Pad1)") (class "Default")
      (node (ref "J1") (pin "1") (pinfunction "1_1") (pintype "passive"))
      (node (ref "J2") (pin "1") (pinfunction "1_1") (pintype "passive"))
    )
    (net (code "159") (name "Net-(J1-Pad2)") (class "Default")
      (node (ref "J1") (pin "2") (pinfunction "2_2") (pintype "passive"))
      (node (ref "J2") (pin "2") (pinfunction "2_2") (pintype "passive"))
    )
    (net (code "160") (name "Net-(OK1A-A)") (class "Default")
      (node (ref "C14") (pin "1") (pinfunction "1_1") (pintype "passive"))
      (node (ref "OK1") (pin "1") (pinfunction "A_1") (pintype "passive"))
      (node (ref "R12") (pin "1") (pinfunction "1_1") (pintype "passive"))
    )
    (net (code "161") (name "Net-(OK1B-A)") (class "Default")
      (node (ref "C13") (pin "1") (pinfunction "1_1") (pintype "passive"))
      (node (ref "OK1") (pin "3") (pinfunction "A_3") (pintype "passive"))
      (node (ref "R11") (pin "1") (pinfunction "1_1") (pintype "passive"))
    )
    (net (code "162") (name "Net-(OK1C-A)") (class "Default")
      (node (ref "C12") (pin "1") (pinfunction "1_1") (pintype "passive"))
      (node (ref "OK1") (pin "5") (pinfunction "A_5") (pintype "passive"))
      (node (ref "R10") (pin "1") (pinfunction "1_1") (pintype "passive"))
    )
    (net (code "163") (name "Net-(OK1D-A)") (class "Default")
      (node (ref "C11") (pin "1") (pinfunction "1_1") (pintype "passive"))
      (node (ref "OK1") (pin "7") (pinfunction "A_7") (pintype "passive"))
      (node (ref "R9") (pin "1") (pinfunction "1_1") (pintype "passive"))
    )
    (net (code "164") (name "Net-(OK2A-A)") (class "Default")
      (node (ref "C18") (pin "1") (pinfunction "1_1") (pintype "passive"))
      (node (ref "OK2") (pin "1") (pinfunction "A_1") (pintype "passive"))
      (node (ref "R16") (pin "1") (pinfunction "1_1") (pintype "passive"))
    )
    (net (code "165") (name "Net-(OK2B-A)") (class "Default")
      (node (ref "C17") (pin "1") (pinfunction "1_1") (pintype "passive"))
      (node (ref "OK2") (pin "3") (pinfunction "A_3") (pintype "passive"))
      (node (ref "R15") (pin "1") (pinfunction "1_1") (pintype "passive"))
    )
    (net (code "166") (name "Net-(OK2C-A)") (class "Default")
      (node (ref "C16") (pin "1") (pinfunction "1_1") (pintype "passive"))
      (node (ref "OK2") (pin "5") (pinfunction "A_5") (pintype "passive"))
      (node (ref "R14") (pin "1") (pinfunction "1_1") (pintype "passive"))
    )
    (net (code "167") (name "Net-(OK2D-A)") (class "Default")
      (node (ref "C15") (pin "1") (pinfunction "1_1") (pintype "passive"))
      (node (ref "OK2") (pin "7") (pinfunction "A_7") (pintype "passive"))
      (node (ref "R13") (pin "1") (pinfunction "1_1") (pintype "passive"))
    )
    (net (code "168") (name "Net-(OK3A-A)") (class "Default")
      (node (ref "C22") (pin "1") (pinfunction "1_1") (pintype "passive"))
      (node (ref "OK3") (pin "1") (pinfunction "A_1") (pintype "passive"))
      (node (ref "R20") (pin "1") (pinfunction "1_1") (pintype "passive"))
    )
    (net (code "169") (name "Net-(OK3B-A)") (class "Default")
      (node (ref "C21") (pin "1") (pinfunction "1_1") (pintype "passive"))
      (node (ref "OK3") (pin "3") (pinfunction "A_3") (pintype "passive"))
      (node (ref "R19") (pin "1") (pinfunction "1_1") (pintype "passive"))
    )
    (net (code "170") (name "Net-(OK3C-A)") (class "Default")
      (node (ref "C20") (pin "1") (pinfunction "1_1") (pintype "passive"))
      (node (ref "OK3") (pin "5") (pinfunction "A_5") (pintype "passive"))
      (node (ref "R18") (pin "1") (pinfunction "1_1") (pintype "passive"))
    )
    (net (code "171") (name "Net-(OK3D-A)") (class "Default")
      (node (ref "C19") (pin "1") (pinfunction "1_1") (pintype "passive"))
      (node (ref "OK3") (pin "7") (pinfunction "A_7") (pintype "passive"))
      (node (ref "R17") (pin "1") (pinfunction "1_1") (pintype "passive"))
    )
    (net (code "172") (name "Net-(OK4A-A)") (class "Default")
      (node (ref "C26") (pin "1") (pinfunction "1_1") (pintype "passive"))
      (node (ref "OK4") (pin "1") (pinfunction "A_1") (pintype "passive"))
      (node (ref "R24") (pin "1") (pinfunction "1_1") (pintype "passive"))
    )
    (net (code "173") (name "Net-(OK4B-A)") (class "Default")
      (node (ref "C25") (pin "1") (pinfunction "1_1") (pintype "passive"))
      (node (ref "OK4") (pin "3") (pinfunction "A_3") (pintype "passive"))
      (node (ref "R23") (pin "1") (pinfunction "1_1") (pintype "passive"))
    )
    (net (code "174") (name "Net-(OK4C-A)") (class "Default")
      (node (ref "C24") (pin "1") (pinfunction "1_1") (pintype "passive"))
      (node (ref "OK4") (pin "5") (pinfunction "A_5") (pintype "passive"))
      (node (ref "R22") (pin "1") (pinfunction "1_1") (pintype "passive"))
    )
    (net (code "175") (name "Net-(OK4D-A)") (class "Default")
      (node (ref "C23") (pin "1") (pinfunction "1_1") (pintype "passive"))
      (node (ref "OK4") (pin "7") (pinfunction "A_7") (pintype "passive"))
      (node (ref "R21") (pin "1") (pinfunction "1_1") (pintype "passive"))
    )
    (net (code "176") (name "Net-(OK5A-A)") (class "Default")
      (node (ref "C30") (pin "1") (pinfunction "1_1") (pintype "passive"))
      (node (ref "OK5") (pin "1") (pinfunction "A_1") (pintype "passive"))
      (node (ref "R28") (pin "1") (pinfunction "1_1") (pintype "passive"))
    )
    (net (code "177") (name "Net-(OK5B-A)") (class "Default")
      (node (ref "C29") (pin "1") (pinfunction "1_1") (pintype "passive"))
      (node (ref "OK5") (pin "3") (pinfunction "A_3") (pintype "passive"))
      (node (ref "R27") (pin "1") (pinfunction "1_1") (pintype "passive"))
    )
    (net (code "178") (name "Net-(OK5C-A)") (class "Default")
      (node (ref "C28") (pin "1") (pinfunction "1_1") (pintype "passive"))
      (node (ref "OK5") (pin "5") (pinfunction "A_5") (pintype "passive"))
      (node (ref "R26") (pin "1") (pinfunction "1_1") (pintype "passive"))
    )
    (net (code "179") (name "Net-(OK5D-A)") (class "Default")
      (node (ref "C27") (pin "1") (pinfunction "1_1") (pintype "passive"))
      (node (ref "OK5") (pin "7") (pinfunction "A_7") (pintype "passive"))
      (node (ref "R25") (pin "1") (pinfunction "1_1") (pintype "passive"))
    )
    (net (code "180") (name "Net-(OK6A-A)") (class "Default")
      (node (ref "C34") (pin "1") (pinfunction "1_1") (pintype "passive"))
      (node (ref "OK6") (pin "1") (pinfunction "A_1") (pintype "passive"))
      (node (ref "R32") (pin "1") (pinfunction "1_1") (pintype "passive"))
    )
    (net (code "181") (name "Net-(OK6B-A)") (class "Default")
      (node (ref "C33") (pin "1") (pinfunction "1_1") (pintype "passive"))
      (node (ref "OK6") (pin "3") (pinfunction "A_3") (pintype "passive"))
      (node (ref "R31") (pin "1") (pinfunction "1_1") (pintype "passive"))
    )
    (net (code "182") (name "Net-(OK6C-A)") (class "Default")
      (node (ref "C32") (pin "1") (pinfunction "1_1") (pintype "passive"))
      (node (ref "OK6") (pin "5") (pinfunction "A_5") (pintype "passive"))
      (node (ref "R30") (pin "1") (pinfunction "1_1") (pintype "passive"))
    )
    (net (code "183") (name "Net-(OK6D-A)") (class "Default")
      (node (ref "C31") (pin "1") (pinfunction "1_1") (pintype "passive"))
      (node (ref "OK6") (pin "7") (pinfunction "A_7") (pintype "passive"))
      (node (ref "R29") (pin "1") (pinfunction "1_1") (pintype "passive"))
    )
    (net (code "184") (name "Net-(OK7A-A)") (class "Default")
      (node (ref "C38") (pin "1") (pinfunction "1_1") (pintype "passive"))
      (node (ref "OK7") (pin "1") (pinfunction "A_1") (pintype "passive"))
      (node (ref "R36") (pin "1") (pinfunction "1_1") (pintype "passive"))
    )
    (net (code "185") (name "Net-(OK7B-A)") (class "Default")
      (node (ref "C37") (pin "1") (pinfunction "1_1") (pintype "passive"))
      (node (ref "OK7") (pin "3") (pinfunction "A_3") (pintype "passive"))
      (node (ref "R35") (pin "1") (pinfunction "1_1") (pintype "passive"))
    )
    (net (code "186") (name "Net-(OK7C-A)") (class "Default")
      (node (ref "C36") (pin "1") (pinfunction "1_1") (pintype "passive"))
      (node (ref "OK7") (pin "5") (pinfunction "A_5") (pintype "passive"))
      (node (ref "R34") (pin "1") (pinfunction "1_1") (pintype "passive"))
    )
    (net (code "187") (name "Net-(OK7D-A)") (class "Default")
      (node (ref "C35") (pin "1") (pinfunction "1_1") (pintype "passive"))
      (node (ref "OK7") (pin "7") (pinfunction "A_7") (pintype "passive"))
      (node (ref "R33") (pin "1") (pinfunction "1_1") (pintype "passive"))
    )
    (net (code "188") (name "Net-(OK8A-A)") (class "Default")
      (node (ref "C42") (pin "1") (pinfunction "1_1") (pintype "passive"))
      (node (ref "OK8") (pin "1") (pinfunction "A_1") (pintype "passive"))
      (node (ref "R40") (pin "1") (pinfunction "1_1") (pintype "passive"))
    )
    (net (code "189") (name "Net-(OK8B-A)") (class "Default")
      (node (ref "C41") (pin "1") (pinfunction "1_1") (pintype "passive"))
      (node (ref "OK8") (pin "3") (pinfunction "A_3") (pintype "passive"))
      (node (ref "R39") (pin "1") (pinfunction "1_1") (pintype "passive"))
    )
    (net (code "190") (name "Net-(OK8C-A)") (class "Default")
      (node (ref "C40") (pin "1") (pinfunction "1_1") (pintype "passive"))
      (node (ref "OK8") (pin "5") (pinfunction "A_5") (pintype "passive"))
      (node (ref "R38") (pin "1") (pinfunction "1_1") (pintype "passive"))
    )
    (net (code "191") (name "Net-(OK8D-A)") (class "Default")
      (node (ref "C39") (pin "1") (pinfunction "1_1") (pintype "passive"))
      (node (ref "OK8") (pin "7") (pinfunction "A_7") (pintype "passive"))
      (node (ref "R37") (pin "1") (pinfunction "1_1") (pintype "passive"))
    )
    (net (code "192") (name "Net-(OK9-C)") (class "Default")
      (node (ref "OK9") (pin "2") (pinfunction "C_2") (pintype "passive"))
      (node (ref "R46") (pin "1") (pinfunction "1_1") (pintype "passive"))
    )
    (net (code "193") (name "Net-(OK9-COL)") (class "Default")
      (node (ref "C46") (pin "1") (pinfunction "1_1") (pintype "passive"))
      (node (ref "OK9") (pin "4") (pinfunction "COL_4") (pintype "passive"))
      (node (ref "R45") (pin "1") (pinfunction "1_1") (pintype "passive"))
    )
    (net (code "194") (name "Net-(POWER-PadC)") (class "Default")
      (node (ref "POWER") (pin "C") (pinfunction "C_C") (pintype "passive"))
      (node (ref "R4") (pin "1") (pinfunction "1_1") (pintype "passive"))
    )
    (net (code "195") (name "Net-(R3-Pad2)") (class "Default")
      (node (ref "R3") (pin "2") (pinfunction "2_2") (pintype "passive"))
      (node (ref "TERM") (pin "1") (pinfunction "1_1") (pintype "passive"))
    )
    (net (code "196") (name "Net-(R5-Pad1)") (class "Default")
      (node (ref "R5") (pin "1") (pinfunction "1_1") (pintype "passive"))
      (node (ref "STATUS") (pin "C") (pinfunction "C_C") (pintype "passive"))
    )
    (net (code "197") (name "Net-(R42-Pad2)") (class "Default")
      (node (ref "R42") (pin "2") (pinfunction "2_2") (pintype "passive"))
      (node (ref "X6") (pin "2") (pinfunction "2_2") (pintype "passive"))
    )
    (net (code "198") (name "Net-(R43-Pad2)") (class "Default")
      (node (ref "R43") (pin "2") (pinfunction "2_2") (pintype "passive"))
      (node (ref "X6") (pin "3") (pinfunction "3_3") (pintype "passive"))
    )
    (net (code "199") (name "Net-(R47-Pad1)") (class "Default")
      (node (ref "R47") (pin "1") (pinfunction "1_1") (pintype "passive"))
      (node (ref "USBRX") (pin "C") (pinfunction "C_C") (pintype "passive"))
    )
    (net (code "200") (name "Net-(R48-Pad1)") (class "Default")
      (node (ref "R48") (pin "1") (pinfunction "1_1") (pintype "passive"))
      (node (ref "USBTX") (pin "C") (pinfunction "C_C") (pintype "passive"))
    )
    (net (code "201") (name "Net-(RN1-Pad1)") (class "Default")
      (node (ref "RN1") (pin "1") (pinfunction "1_1") (pintype "passive"))
      (node (ref "T1") (pin "A") (pinfunction "A_A") (pintype "passive"))
    )
    (net (code "202") (name "Net-(RN1B-1)") (class "Default")
      (node (ref "RN1") (pin "2") (pinfunction "1_2") (pintype "passive"))
      (node (ref "T2") (pin "A") (pinfunction "A_A") (pintype "passive"))
    )
    (net (code "203") (name "Net-(RN1C-1)") (class "Default")
      (node (ref "RN1") (pin "3") (pinfunction "1_3") (pintype "passive"))
      (node (ref "T3") (pin "A") (pinfunction "A_A") (pintype "passive"))
    )
    (net (code "204") (name "Net-(RN1D-1)") (class "Default")
      (node (ref "RN1") (pin "4") (pinfunction "1_4") (pintype "passive"))
      (node (ref "T4") (pin "A") (pinfunction "A_A") (pintype "passive"))
    )
    (net (code "205") (name "Net-(RN2-Pad1)") (class "Default")
      (node (ref "RN2") (pin "1") (pinfunction "1_1") (pintype "passive"))
      (node (ref "T5") (pin "A") (pinfunction "A_A") (pintype "passive"))
    )
    (net (code "206") (name "Net-(RN2B-1)") (class "Default")
      (node (ref "RN2") (pin "2") (pinfunction "1_2") (pintype "passive"))
      (node (ref "T6") (pin "A") (pinfunction "A_A") (pintype "passive"))
    )
    (net (code "207") (name "Net-(RN2C-1)") (class "Default")
      (node (ref "RN2") (pin "3") (pinfunction "1_3") (pintype "passive"))
      (node (ref "T7") (pin "A") (pinfunction "A_A") (pintype "passive"))
    )
    (net (code "208") (name "Net-(RN2D-1)") (class "Default")
      (node (ref "RN2") (pin "4") (pinfunction "1_4") (pintype "passive"))
      (node (ref "T8") (pin "A") (pinfunction "A_A") (pintype "passive"))
    )
    (net (code "209") (name "Net-(RN3-Pad1)") (class "Default")
      (node (ref "RN3") (pin "1") (pinfunction "1_1") (pintype "passive"))
      (node (ref "T9") (pin "A") (pinfunction "A_A") (pintype "passive"))
    )
    (net (code "210") (name "Net-(RN3B-1)") (class "Default")
      (node (ref "RN3") (pin "2") (pinfunction "1_2") (pintype "passive"))
      (node (ref "T10") (pin "A") (pinfunction "A_A") (pintype "passive"))
    )
    (net (code "211") (name "Net-(RN3C-1)") (class "Default")
      (node (ref "RN3") (pin "3") (pinfunction "1_3") (pintype "passive"))
      (node (ref "T11") (pin "A") (pinfunction "A_A") (pintype "passive"))
    )
    (net (code "212") (name "Net-(RN3D-1)") (class "Default")
      (node (ref "RN3") (pin "4") (pinfunction "1_4") (pintype "passive"))
      (node (ref "T12") (pin "A") (pinfunction "A_A") (pintype "passive"))
    )
    (net (code "213") (name "Net-(RN4-Pad1)") (class "Default")
      (node (ref "RN4") (pin "1") (pinfunction "1_1") (pintype "passive"))
      (node (ref "T13") (pin "A") (pinfunction "A_A") (pintype "passive"))
    )
    (net (code "214") (name "Net-(RN4B-1)") (class "Default")
      (node (ref "RN4") (pin "2") (pinfunction "1_2") (pintype "passive"))
      (node (ref "T14") (pin "A") (pinfunction "A_A") (pintype "passive"))
    )
    (net (code "215") (name "Net-(RN4C-1)") (class "Default")
      (node (ref "RN4") (pin "3") (pinfunction "1_3") (pintype "passive"))
      (node (ref "T15") (pin "A") (pinfunction "A_A") (pintype "passive"))
    )
    (net (code "216") (name "Net-(RN4D-1)") (class "Default")
      (node (ref "RN4") (pin "4") (pinfunction "1_4") (pintype "passive"))
      (node (ref "T16") (pin "A") (pinfunction "A_A") (pintype "passive"))
    )
    (net (code "217") (name "Net-(RN5-Pad1)") (class "Default")
      (node (ref "RN5") (pin "1") (pinfunction "1_1") (pintype "passive"))
      (node (ref "T17") (pin "A") (pinfunction "A_A") (pintype "passive"))
    )
    (net (code "218") (name "Net-(RN5B-1)") (class "Default")
      (node (ref "RN5") (pin "2") (pinfunction "1_2") (pintype "passive"))
      (node (ref "T18") (pin "A") (pinfunction "A_A") (pintype "passive"))
    )
    (net (code "219") (name "Net-(RN5C-1)") (class "Default")
      (node (ref "RN5") (pin "3") (pinfunction "1_3") (pintype "passive"))
      (node (ref "T19") (pin "A") (pinfunction "A_A") (pintype "passive"))
    )
    (net (code "220") (name "Net-(RN5D-1)") (class "Default")
      (node (ref "RN5") (pin "4") (pinfunction "1_4") (pintype "passive"))
      (node (ref "T20") (pin "A") (pinfunction "A_A") (pintype "passive"))
    )
    (net (code "221") (name "Net-(RN6-Pad1)") (class "Default")
      (node (ref "RN6") (pin "1") (pinfunction "1_1") (pintype "passive"))
      (node (ref "T21") (pin "A") (pinfunction "A_A") (pintype "passive"))
    )
    (net (code "222") (name "Net-(RN6B-1)") (class "Default")
      (node (ref "RN6") (pin "2") (pinfunction "1_2") (pintype "passive"))
      (node (ref "T22") (pin "A") (pinfunction "A_A") (pintype "passive"))
    )
    (net (code "223") (name "Net-(RN6C-1)") (class "Default")
      (node (ref "RN6") (pin "3") (pinfunction "1_3") (pintype "passive"))
      (node (ref "T23") (pin "A") (pinfunction "A_A") (pintype "passive"))
    )
    (net (code "224") (name "Net-(RN6D-1)") (class "Default")
      (node (ref "RN6") (pin "4") (pinfunction "1_4") (pintype "passive"))
      (node (ref "T24") (pin "A") (pinfunction "A_A") (pintype "passive"))
    )
    (net (code "225") (name "Net-(RN7-Pad1)") (class "Default")
      (node (ref "RN7") (pin "1") (pinfunction "1_1") (pintype "passive"))
      (node (ref "T25") (pin "A") (pinfunction "A_A") (pintype "passive"))
    )
    (net (code "226") (name "Net-(RN7B-1)") (class "Default")
      (node (ref "RN7") (pin "2") (pinfunction "1_2") (pintype "passive"))
      (node (ref "T26") (pin "A") (pinfunction "A_A") (pintype "passive"))
    )
    (net (code "227") (name "Net-(RN7C-1)") (class "Default")
      (node (ref "RN7") (pin "3") (pinfunction "1_3") (pintype "passive"))
      (node (ref "T27") (pin "A") (pinfunction "A_A") (pintype "passive"))
    )
    (net (code "228") (name "Net-(RN7D-1)") (class "Default")
      (node (ref "RN7") (pin "4") (pinfunction "1_4") (pintype "passive"))
      (node (ref "T28") (pin "A") (pinfunction "A_A") (pintype "passive"))
    )
    (net (code "229") (name "Net-(RN8-Pad1)") (class "Default")
      (node (ref "RN8") (pin "1") (pinfunction "1_1") (pintype "passive"))
      (node (ref "T29") (pin "A") (pinfunction "A_A") (pintype "passive"))
    )
    (net (code "230") (name "Net-(RN8B-1)") (class "Default")
      (node (ref "RN8") (pin "2") (pinfunction "1_2") (pintype "passive"))
      (node (ref "T30") (pin "A") (pinfunction "A_A") (pintype "passive"))
    )
    (net (code "231") (name "Net-(RN8C-1)") (class "Default")
      (node (ref "RN8") (pin "3") (pinfunction "1_3") (pintype "passive"))
      (node (ref "T31") (pin "A") (pinfunction "A_A") (pintype "passive"))
    )
    (net (code "232") (name "Net-(RN8D-1)") (class "Default")
      (node (ref "RN8") (pin "4") (pinfunction "1_4") (pintype "passive"))
      (node (ref "T32") (pin "A") (pinfunction "A_A") (pintype "passive"))
    )
    (net (code "233") (name "OSC1") (class "Default")
      (node (ref "C7") (pin "1") (pinfunction "1_1") (pintype "passive"))
      (node (ref "IC3") (pin "8") (pinfunction "OSC1_8") (pintype "input"))
      (node (ref "Q2") (pin "1") (pinfunction "1_1") (pintype "passive"))
      (node (ref "R2") (pin "1") (pinfunction "1_1") (pintype "passive"))
    )
    (net (code "234") (name "OSC2") (class "Default")
      (node (ref "C8") (pin "1") (pinfunction "1_1") (pintype "passive"))
      (node (ref "IC3") (pin "7") (pinfunction "OSC2_7") (pintype "output"))
      (node (ref "Q2") (pin "3") (pinfunction "2_3") (pintype "passive"))
      (node (ref "R2") (pin "2") (pinfunction "2_2") (pintype "passive"))
    )
    (net (code "235") (name "RESET") (class "Default")
      (node (ref "C46") (pin "2") (pinfunction "2_2") (pintype "passive"))
      (node (ref "IC1") (pin "30") (pinfunction "~{RESET}_30") (pintype "input"))
      (node (ref "IC3") (pin "17") (pinfunction "~{RESET}_17") (pintype "input"))
      (node (ref "ISP") (pin "5") (pinfunction "S_5") (pintype "passive"))
      (node (ref "R8") (pin "1") (pinfunction "1_1") (pintype "passive"))
      (node (ref "U$15") (pin "P$3") (pinfunction "P$3_P$3") (pintype "bidirectional"))
      (node (ref "U$15") (pin "P$4") (pinfunction "P$4_P$4") (pintype "bidirectional"))
    )
    (net (code "236") (name "RESET2") (class "Default")
      (node (ref "IC4") (pin "24") (pinfunction "PC1//~{RESET}_24") (pintype "bidirectional"))
      (node (ref "R44") (pin "2") (pinfunction "2_2") (pintype "passive"))
      (node (ref "RS") (pin "TP") (pinfunction "TP_TP") (pintype "input"))
    )
    (net (code "237") (name "RXCAN") (class "Default")
      (node (ref "IC2") (pin "4") (pinfunction "RXD_4") (pintype "output"))
      (node (ref "IC3") (pin "2") (pinfunction "RXCAN_2") (pintype "input"))
    )
    (net (code "238") (name "RXD") (class "Default")
      (node (ref "IC1") (pin "2") (pinfunction "(RXD0/PCINT8)_PE0_2") (pintype "bidirectional"))
      (node (ref "IC5") (pin "2") (pinfunction "VOA_2") (pintype "output"))
    )
    (net (code "239") (name "RXDUSB") (class "Default")
      (node (ref "IC4") (pin "8") (pinfunction "PD2_8") (pintype "bidirectional"))
      (node (ref "IC5") (pin "6") (pinfunction "VOB_6") (pintype "output"))
    )
    (net (code "240") (name "RXLED") (class "Default")
      (node (ref "IC4") (pin "10") (pinfunction "PD4_10") (pintype "bidirectional"))
      (node (ref "R47") (pin "2") (pinfunction "2_2") (pintype "passive"))
    )
    (net (code "241") (name "SCK") (class "Default")
      (node (ref "IC1") (pin "20") (pinfunction "(SCK/PCINT1)_PB1_20") (pintype "bidirectional"))
      (node (ref "IC3") (pin "13") (pinfunction "SCK_13") (pintype "input"))
      (node (ref "ISP") (pin "3") (pinfunction "S_3") (pintype "passive"))
    )
    (net (code "242") (name "SCK2") (class "Default")
      (node (ref "IC4") (pin "15") (pinfunction "PB1_15") (pintype "bidirectional"))
      (node (ref "SCK") (pin "TP") (pinfunction "TP_TP") (pintype "input"))
    )
    (net (code "243") (name "SCL") (class "Default")
      (node (ref "IC1") (pin "43") (pinfunction "(SCL/INT0)_PD0_43") (pintype "bidirectional"))
      (node (ref "I²C") (pin "2") (pinfunction "S_2") (pintype "passive"))
      (node (ref "R6") (pin "1") (pinfunction "1_1") (pintype "passive"))
    )
    (net (code "244") (name "SDA") (class "Default")
      (node (ref "IC1") (pin "44") (pinfunction "(SDA/INT1)_PD1_44") (pintype "bidirectional"))
      (node (ref "I²C") (pin "1") (pinfunction "S_1") (pintype "passive"))
      (node (ref "R7") (pin "1") (pinfunction "1_1") (pintype "passive"))
    )
    (net (code "245") (name "STATUS") (class "Default")
      (node (ref "IC1") (pin "46") (pinfunction "(TXD1/INT3)_PD3_46") (pintype "bidirectional"))
      (node (ref "STATUS") (pin "A") (pinfunction "A_A") (pintype "passive"))
    )
    (net (code "246") (name "TXCAN") (class "Default")
      (node (ref "IC2") (pin "1") (pinfunction "TXD_1") (pintype "input"))
      (node (ref "IC3") (pin "1") (pinfunction "TXCAN_1") (pintype "output"))
    )
    (net (code "247") (name "TXD") (class "Default")
      (node (ref "IC1") (pin "3") (pinfunction "(TXD0)_PE1_3") (pintype "bidirectional"))
      (node (ref "IC5") (pin "3") (pinfunction "VIB_3") (pintype "input"))
    )
    (net (code "248") (name "TXDUSB") (class "Default")
      (node (ref "IC4") (pin "9") (pinfunction "PD3_9") (pintype "bidirectional"))
      (node (ref "IC5") (pin "7") (pinfunction "VIA_7") (pintype "input"))
    )
    (net (code "249") (name "TXLED") (class "Default")
      (node (ref "IC4") (pin "11") (pinfunction "PD5_11") (pintype "bidirectional"))
      (node (ref "R48") (pin "2") (pinfunction "2_2") (pintype "passive"))
    )
    (net (code "250") (name "VCC") (class "Default")
      (node (ref "C1") (pin "1") (pinfunction "1_1") (pintype "passive"))
      (node (ref "C10") (pin "1") (pinfunction "1_1") (pintype "passive"))
      (node (ref "C2") (pin "1") (pinfunction "1_1") (pintype "passive"))
      (node (ref "C3") (pin "1") (pinfunction "1_1") (pintype "passive"))
      (node (ref "C6") (pin "1") (pinfunction "1_1") (pintype "passive"))
      (node (ref "IC1") (pin "10") (pinfunction "VCC_3_10") (pintype "power_in"))
      (node (ref "IC1") (pin "100") (pinfunction "AVCC_100") (pintype "power_in"))
      (node (ref "IC1") (pin "31") (pinfunction "VCC_2_31") (pintype "power_in"))
      (node (ref "IC1") (pin "61") (pinfunction "VCC_4_61") (pintype "power_in"))
      (node (ref "IC1") (pin "80") (pinfunction "VCC_80") (pintype "power_in"))
      (node (ref "IC2") (pin "3") (pinfunction "VDD_3") (pintype "power_in"))
      (node (ref "IC2") (pin "5") (pinfunction "VREF_5") (pintype "output"))
      (node (ref "IC3") (pin "18") (pinfunction "VDD_18") (pintype "power_in"))
      (node (ref "IC5") (pin "1") (pinfunction "VDD1_1") (pintype "power_in"))
      (node (ref "IC8") (pin "2") (pinfunction "VO_2") (pintype "passive"))
      (node (ref "ISP") (pin "2") (pinfunction "S_2") (pintype "passive"))
      (node (ref "POWER") (pin "A") (pinfunction "A_A") (pintype "passive"))
      (node (ref "R45") (pin "2") (pinfunction "2_2") (pintype "passive"))
      (node (ref "R6") (pin "2") (pinfunction "2_2") (pintype "passive"))
      (node (ref "R7") (pin "2") (pinfunction "2_2") (pintype "passive"))
      (node (ref "R8") (pin "2") (pinfunction "2_2") (pintype "passive"))
      (node (ref "RN1") (pin "5") (pinfunction "2_5") (pintype "passive"))
      (node (ref "RN1") (pin "6") (pinfunction "2_6") (pintype "passive"))
      (node (ref "RN1") (pin "7") (pinfunction "2_7") (pintype "passive"))
      (node (ref "RN1") (pin "8") (pinfunction "2_8") (pintype "passive"))
      (node (ref "RN2") (pin "5") (pinfunction "2_5") (pintype "passive"))
      (node (ref "RN2") (pin "6") (pinfunction "2_6") (pintype "passive"))
      (node (ref "RN2") (pin "7") (pinfunction "2_7") (pintype "passive"))
      (node (ref "RN2") (pin "8") (pinfunction "2_8") (pintype "passive"))
      (node (ref "RN3") (pin "5") (pinfunction "2_5") (pintype "passive"))
      (node (ref "RN3") (pin "6") (pinfunction "2_6") (pintype "passive"))
      (node (ref "RN3") (pin "7") (pinfunction "2_7") (pintype "passive"))
      (node (ref "RN3") (pin "8") (pinfunction "2_8") (pintype "passive"))
      (node (ref "RN4") (pin "5") (pinfunction "2_5") (pintype "passive"))
      (node (ref "RN4") (pin "6") (pinfunction "2_6") (pintype "passive"))
      (node (ref "RN4") (pin "7") (pinfunction "2_7") (pintype "passive"))
      (node (ref "RN4") (pin "8") (pinfunction "2_8") (pintype "passive"))
      (node (ref "RN5") (pin "5") (pinfunction "2_5") (pintype "passive"))
      (node (ref "RN5") (pin "6") (pinfunction "2_6") (pintype "passive"))
      (node (ref "RN5") (pin "7") (pinfunction "2_7") (pintype "passive"))
      (node (ref "RN5") (pin "8") (pinfunction "2_8") (pintype "passive"))
      (node (ref "RN6") (pin "5") (pinfunction "2_5") (pintype "passive"))
      (node (ref "RN6") (pin "6") (pinfunction "2_6") (pintype "passive"))
      (node (ref "RN6") (pin "7") (pinfunction "2_7") (pintype "passive"))
      (node (ref "RN6") (pin "8") (pinfunction "2_8") (pintype "passive"))
      (node (ref "RN7") (pin "5") (pinfunction "2_5") (pintype "passive"))
      (node (ref "RN7") (pin "6") (pinfunction "2_6") (pintype "passive"))
      (node (ref "RN7") (pin "7") (pinfunction "2_7") (pintype "passive"))
      (node (ref "RN7") (pin "8") (pinfunction "2_8") (pintype "passive"))
      (node (ref "RN8") (pin "5") (pinfunction "2_5") (pintype "passive"))
      (node (ref "RN8") (pin "6") (pinfunction "2_6") (pintype "passive"))
      (node (ref "RN8") (pin "7") (pinfunction "2_7") (pintype "passive"))
      (node (ref "RN8") (pin "8") (pinfunction "2_8") (pintype "passive"))
    )
    (net (code "251") (name "VCC2") (class "Default")
      (node (ref "C47") (pin "1") (pinfunction "1_1") (pintype "passive"))
      (node (ref "IC4") (pin "31") (pinfunction "UVCC_31") (pintype "power_in"))
      (node (ref "IC4") (pin "32") (pinfunction "AVCC_32") (pintype "power_in"))
      (node (ref "IC4") (pin "4") (pinfunction "VCC_4") (pintype "power_in"))
      (node (ref "IC5") (pin "8") (pinfunction "VDD2_8") (pintype "power_in"))
      (node (ref "OK9") (pin "1") (pinfunction "A_1") (pintype "passive"))
      (node (ref "R44") (pin "1") (pinfunction "1_1") (pintype "passive"))
      (node (ref "USBRX") (pin "A") (pinfunction "A_A") (pintype "passive"))
      (node (ref "USBTX") (pin "A") (pinfunction "A_A") (pintype "passive"))
      (node (ref "VCC") (pin "TP") (pinfunction "TP_TP") (pintype "input"))
      (node (ref "X6") (pin "1") (pinfunction "1_1") (pintype "passive"))
    )
    (net (code "252") (name "XTAL1") (class "Default")
      (node (ref "C4") (pin "1") (pinfunction "1_1") (pintype "passive"))
      (node (ref "IC1") (pin "34") (pinfunction "XTAL1_34") (pintype "input"))
      (node (ref "Q1") (pin "1") (pinfunction "1_1") (pintype "passive"))
      (node (ref "R1") (pin "1") (pinfunction "1_1") (pintype "passive"))
    )
    (net (code "253") (name "XTAL2") (class "Default")
      (node (ref "C5") (pin "1") (pinfunction "1_1") (pintype "passive"))
      (node (ref "IC1") (pin "33") (pinfunction "XTAL2_33") (pintype "output"))
      (node (ref "Q1") (pin "3") (pinfunction "2_3") (pintype "passive"))
      (node (ref "R1") (pin "2") (pinfunction "2_2") (pintype "passive"))
    )
    (net (code "254") (name "unconnected-(H1-MOUNT-PadB3,2)") (class "Default")
      (node (ref "H1") (pin "B3,2") (pinfunction "MOUNT_B3,2") (pintype "passive"))
    )
    (net (code "255") (name "unconnected-(H2-MOUNT-PadB3,2)") (class "Default")
      (node (ref "H2") (pin "B3,2") (pinfunction "MOUNT_B3,2") (pintype "passive"))
    )
    (net (code "256") (name "unconnected-(H3-MOUNT-PadB3,2)") (class "Default")
      (node (ref "H3") (pin "B3,2") (pinfunction "MOUNT_B3,2") (pintype "passive"))
    )
    (net (code "257") (name "unconnected-(H4-MOUNT-PadB3,2)") (class "Default")
      (node (ref "H4") (pin "B3,2") (pinfunction "MOUNT_B3,2") (pintype "passive"))
    )
    (net (code "258") (name "unconnected-(H5-MOUNT-PadB3,2)") (class "Default")
      (node (ref "H5") (pin "B3,2") (pinfunction "MOUNT_B3,2") (pintype "passive"))
    )
    (net (code "259") (name "unconnected-(H6-MOUNT-PadB3,2)") (class "Default")
      (node (ref "H6") (pin "B3,2") (pinfunction "MOUNT_B3,2") (pintype "passive"))
    )
    (net (code "260") (name "unconnected-(IC1-(OC0B)_PG5-Pad1)") (class "Default")
      (node (ref "IC1") (pin "1") (pinfunction "(OC0B)_PG5_1") (pintype "bidirectional"))
    )
    (net (code "261") (name "unconnected-(IC1-(OC1A{slash}PCINT5)_PB5-Pad24)") (class "Default")
      (node (ref "IC1") (pin "24") (pinfunction "(OC1A/PCINT5)_PB5_24") (pintype "bidirectional"))
    )
    (net (code "262") (name "unconnected-(IC1-(OC2A{slash}PCINT4)_PB4-Pad23)") (class "Default")
      (node (ref "IC1") (pin "23") (pinfunction "(OC2A/PCINT4)_PB4_23") (pintype "bidirectional"))
    )
    (net (code "263") (name "unconnected-(IC1-(TOSC1)_PG4-Pad29)") (class "Default")
      (node (ref "IC1") (pin "29") (pinfunction "(TOSC1)_PG4_29") (pintype "bidirectional"))
    )
    (net (code "264") (name "unconnected-(IC1-(TOSC2)_PG3-Pad28)") (class "Default")
      (node (ref "IC1") (pin "28") (pinfunction "(TOSC2)_PG3_28") (pintype "bidirectional"))
    )
    (net (code "265") (name "unconnected-(IC1-AREF-Pad98)") (class "Default")
      (node (ref "IC1") (pin "98") (pinfunction "AREF_98") (pintype "input"))
    )
    (net (code "266") (name "unconnected-(IC1-PG0_(~{WR})-Pad51)") (class "Default")
      (node (ref "IC1") (pin "51") (pinfunction "PG0_(~{WR})_51") (pintype "bidirectional"))
    )
    (net (code "267") (name "unconnected-(IC1-PG1_(~{RD})-Pad52)") (class "Default")
      (node (ref "IC1") (pin "52") (pinfunction "PG1_(~{RD})_52") (pintype "bidirectional"))
    )
    (net (code "268") (name "unconnected-(IC1-PG2_(ALE)-Pad70)") (class "Default")
      (node (ref "IC1") (pin "70") (pinfunction "PG2_(ALE)_70") (pintype "bidirectional"))
    )
    (net (code "269") (name "unconnected-(IC3-CLKOUT{slash}SOF-Pad3)") (class "Default")
      (node (ref "IC3") (pin "3") (pinfunction "CLKOUT/SOF_3") (pintype "output"))
    )
    (net (code "270") (name "unconnected-(IC3-~{RX0BF}-Pad11)") (class "Default")
      (node (ref "IC3") (pin "11") (pinfunction "~{RX0BF}_11") (pintype "output"))
    )
    (net (code "271") (name "unconnected-(IC3-~{RX1BF}-Pad10)") (class "Default")
      (node (ref "IC3") (pin "10") (pinfunction "~{RX1BF}_10") (pintype "output"))
    )
    (net (code "272") (name "unconnected-(IC3-~{TX0RTS}-Pad4)") (class "Default")
      (node (ref "IC3") (pin "4") (pinfunction "~{TX0RTS}_4") (pintype "input"))
    )
    (net (code "273") (name "unconnected-(IC3-~{TX1RTS}-Pad5)") (class "Default")
      (node (ref "IC3") (pin "5") (pinfunction "~{TX1RTS}_5") (pintype "input"))
    )
    (net (code "274") (name "unconnected-(IC3-~{TX2RTS}-Pad6)") (class "Default")
      (node (ref "IC3") (pin "6") (pinfunction "~{TX2RTS}_6") (pintype "input"))
    )
    (net (code "275") (name "unconnected-(IC4-PB0-Pad14)") (class "Default")
      (node (ref "IC4") (pin "14") (pinfunction "PB0_14") (pintype "bidirectional"))
    )
    (net (code "276") (name "unconnected-(IC4-PB4-Pad18)") (class "Default")
      (node (ref "IC4") (pin "18") (pinfunction "PB4_18") (pintype "bidirectional"))
    )
    (net (code "277") (name "unconnected-(IC4-PB5-Pad19)") (class "Default")
      (node (ref "IC4") (pin "19") (pinfunction "PB5_19") (pintype "bidirectional"))
    )
    (net (code "278") (name "unconnected-(IC4-PB6-Pad20)") (class "Default")
      (node (ref "IC4") (pin "20") (pinfunction "PB6_20") (pintype "bidirectional"))
    )
    (net (code "279") (name "unconnected-(IC4-PB7-Pad21)") (class "Default")
      (node (ref "IC4") (pin "21") (pinfunction "PB7_21") (pintype "bidirectional"))
    )
    (net (code "280") (name "unconnected-(IC4-PC0-Pad2)") (class "Default")
      (node (ref "IC4") (pin "2") (pinfunction "PC0_2") (pintype "bidirectional"))
    )
    (net (code "281") (name "unconnected-(IC4-PC2-Pad5)") (class "Default")
      (node (ref "IC4") (pin "5") (pinfunction "PC2_5") (pintype "bidirectional"))
    )
    (net (code "282") (name "unconnected-(IC4-PC4-Pad26)") (class "Default")
      (node (ref "IC4") (pin "26") (pinfunction "PC4_26") (pintype "bidirectional"))
    )
    (net (code "283") (name "unconnected-(IC4-PC5-Pad25)") (class "Default")
      (node (ref "IC4") (pin "25") (pinfunction "PC5_25") (pintype "bidirectional"))
    )
    (net (code "284") (name "unconnected-(IC4-PC6-Pad23)") (class "Default")
      (node (ref "IC4") (pin "23") (pinfunction "PC6_23") (pintype "bidirectional"))
    )
    (net (code "285") (name "unconnected-(IC4-PC7-Pad22)") (class "Default")
      (node (ref "IC4") (pin "22") (pinfunction "PC7_22") (pintype "bidirectional"))
    )
    (net (code "286") (name "unconnected-(IC4-PD1-Pad7)") (class "Default")
      (node (ref "IC4") (pin "7") (pinfunction "PD1_7") (pintype "bidirectional"))
    )
    (net (code "287") (name "unconnected-(IC4-PD6-Pad12)") (class "Default")
      (node (ref "IC4") (pin "12") (pinfunction "PD6_12") (pintype "bidirectional"))
    )
    (net (code "288") (name "unconnected-(X6-Pad4)") (class "Default")
      (node (ref "X6") (pin "4") (pinfunction "4_4") (pintype "passive"))
    )
  )
)
